# FindMeSAT_MB_1V2.net
KiCad netlist of a schematic drawn in EAGLE
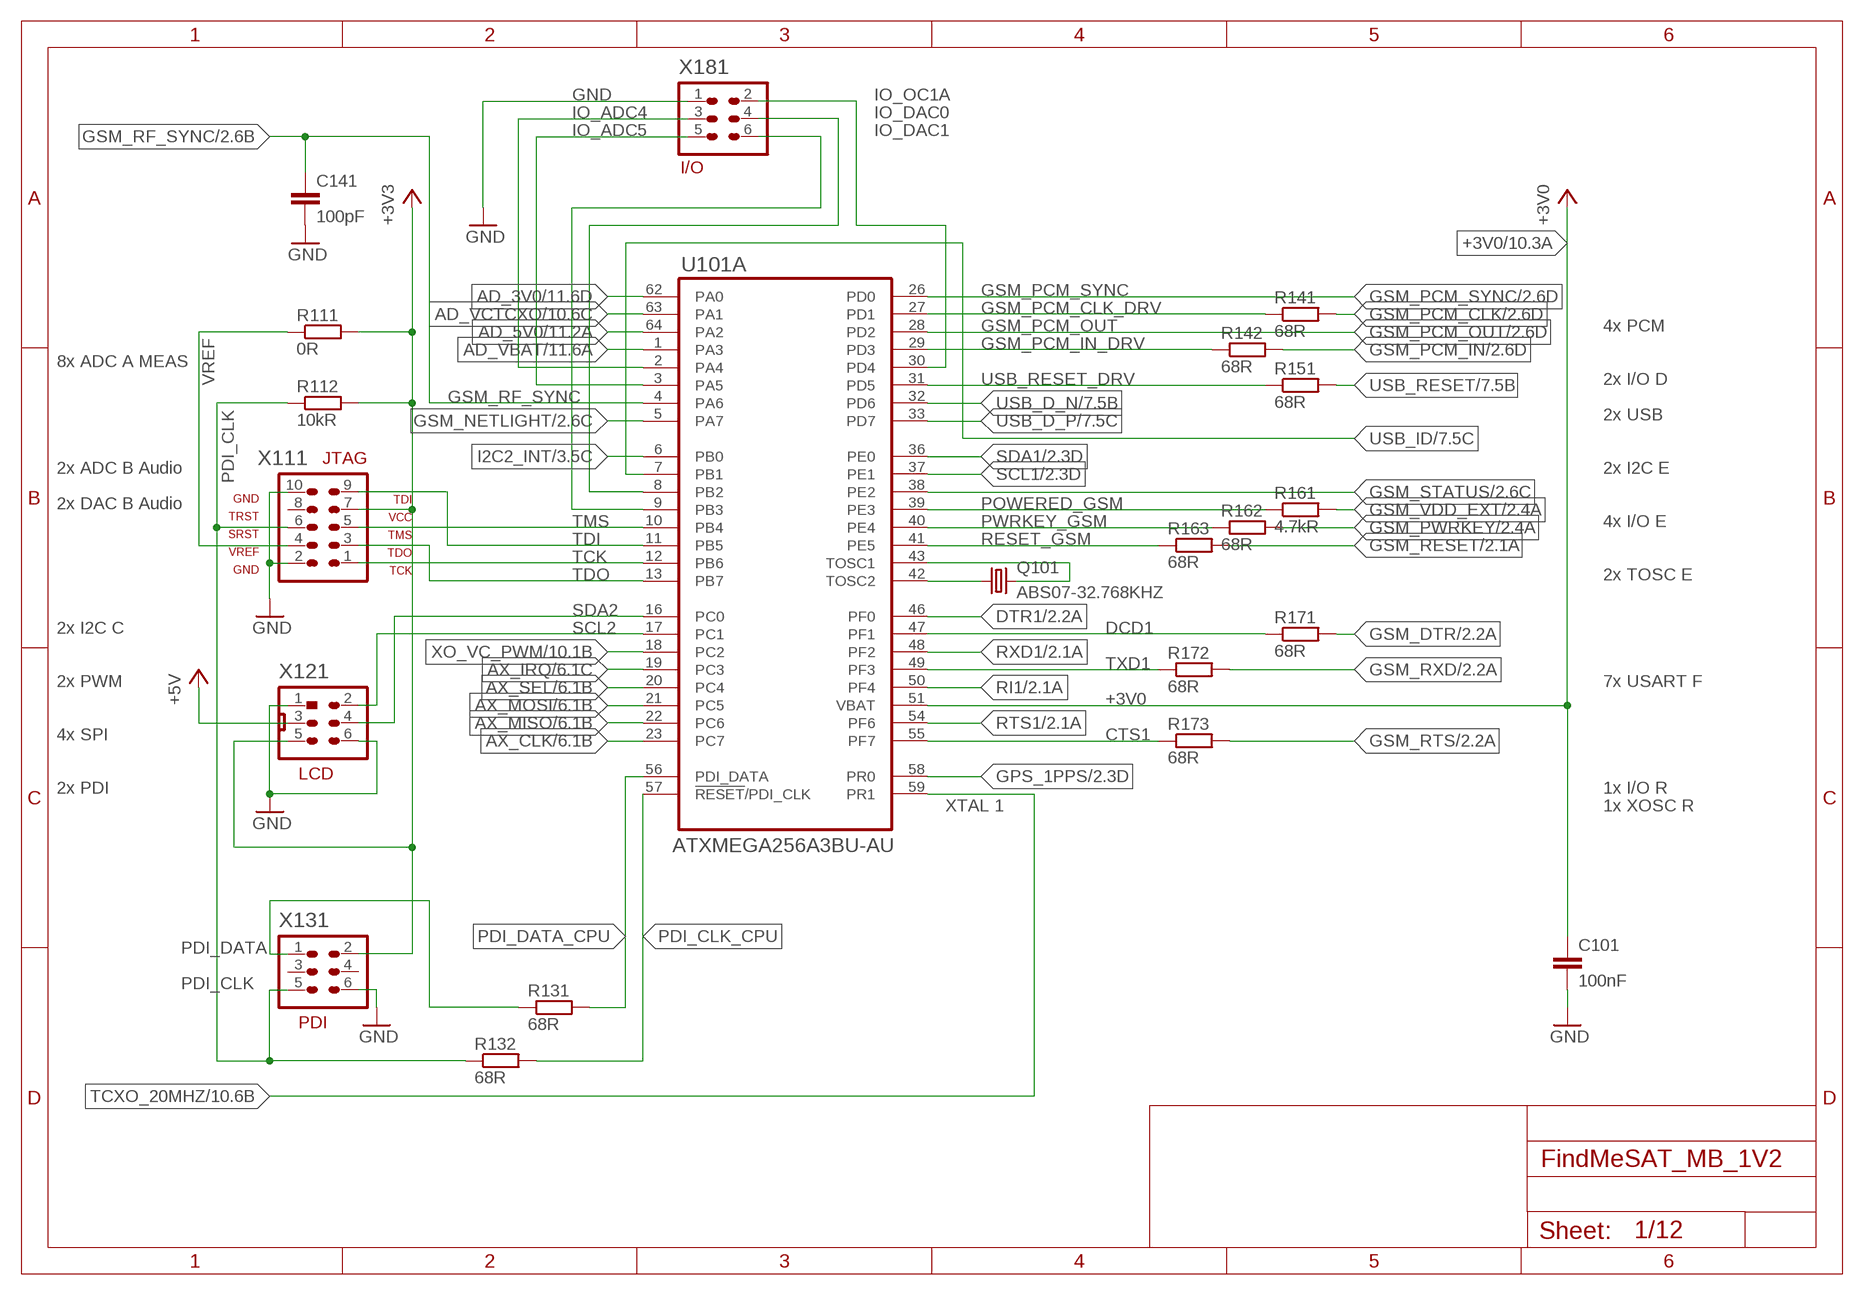
[diagram p0: schematic, sheet 1]
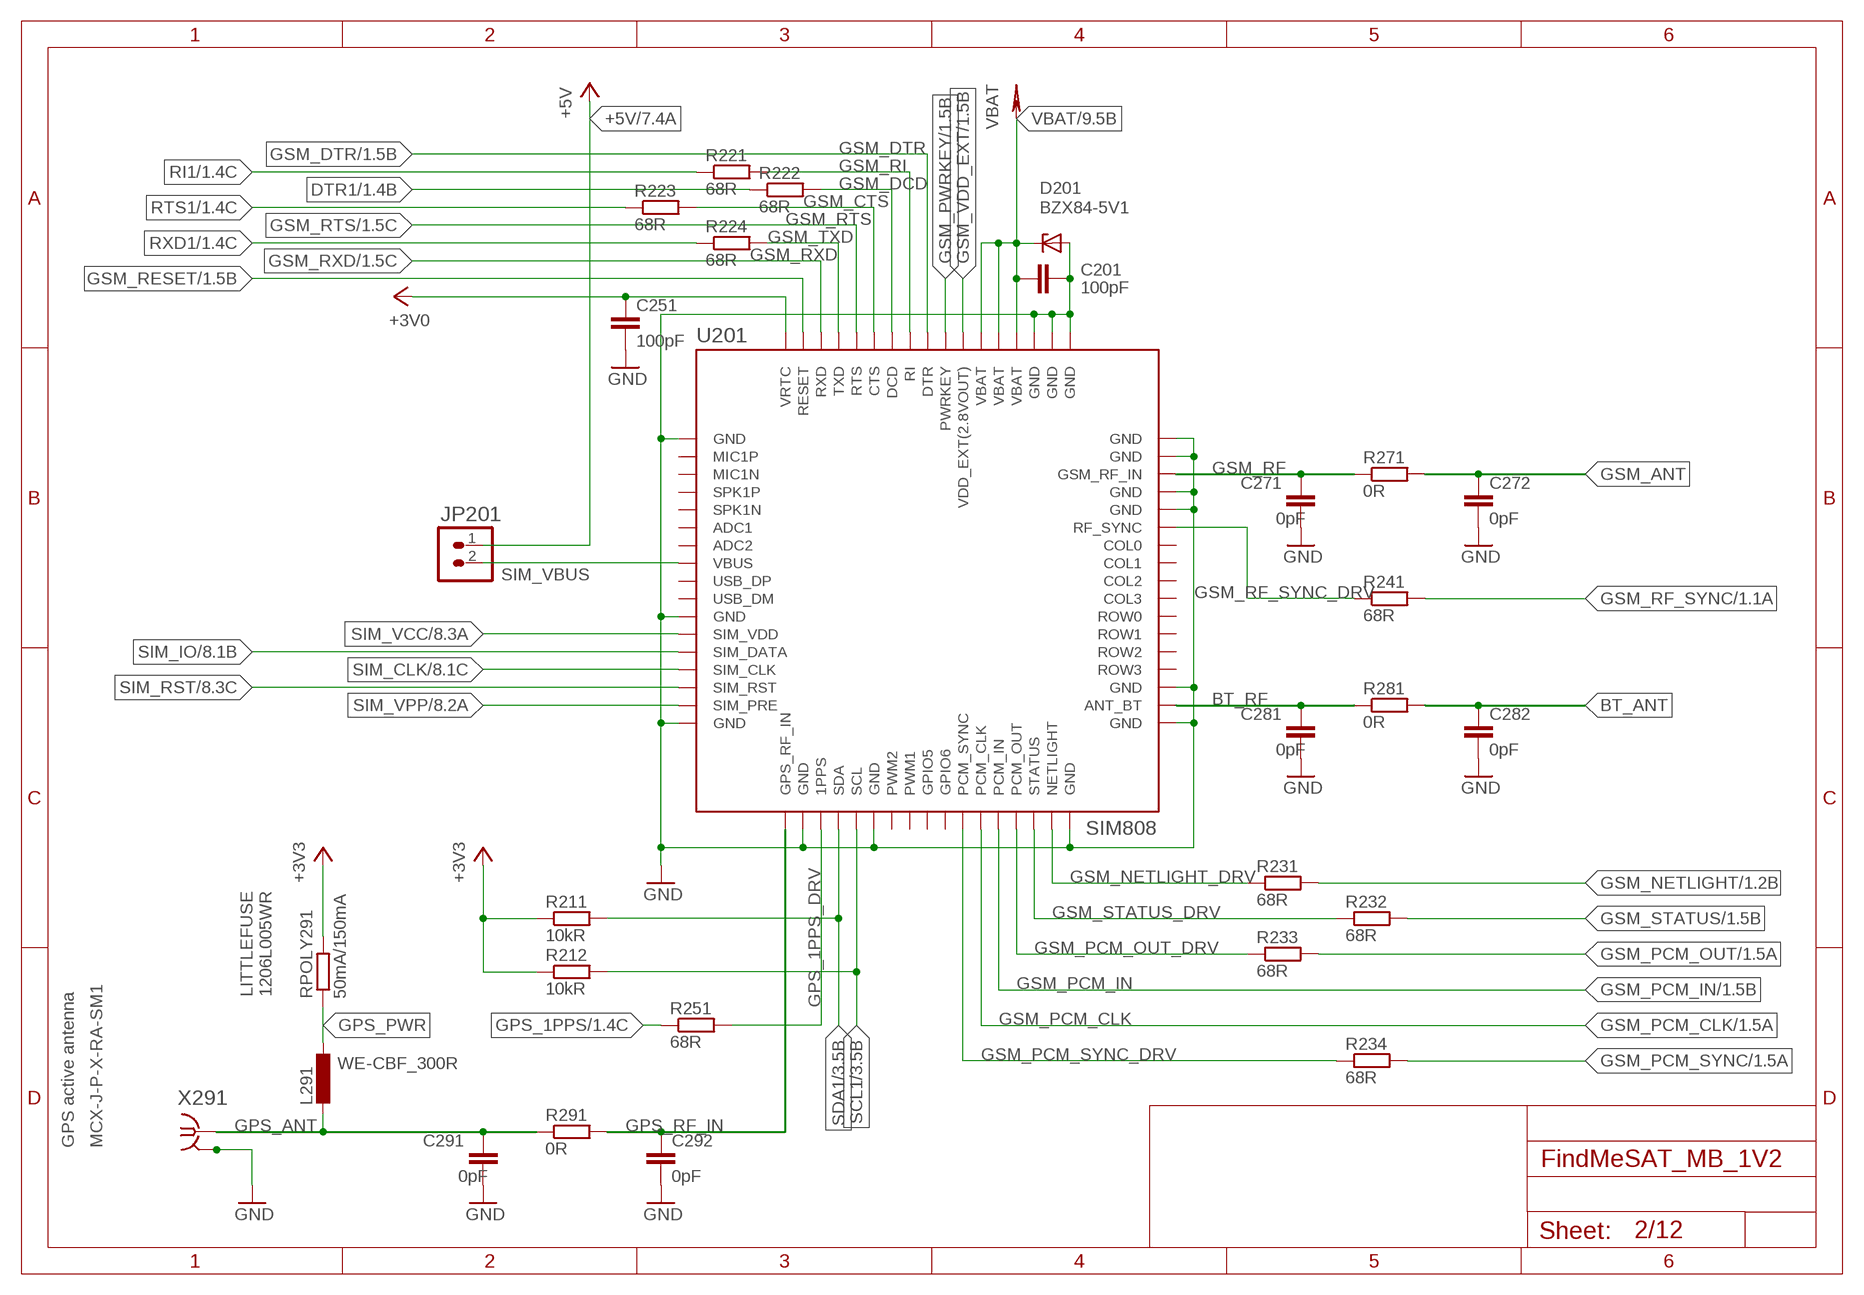
[diagram p1: schematic, sheet 2]
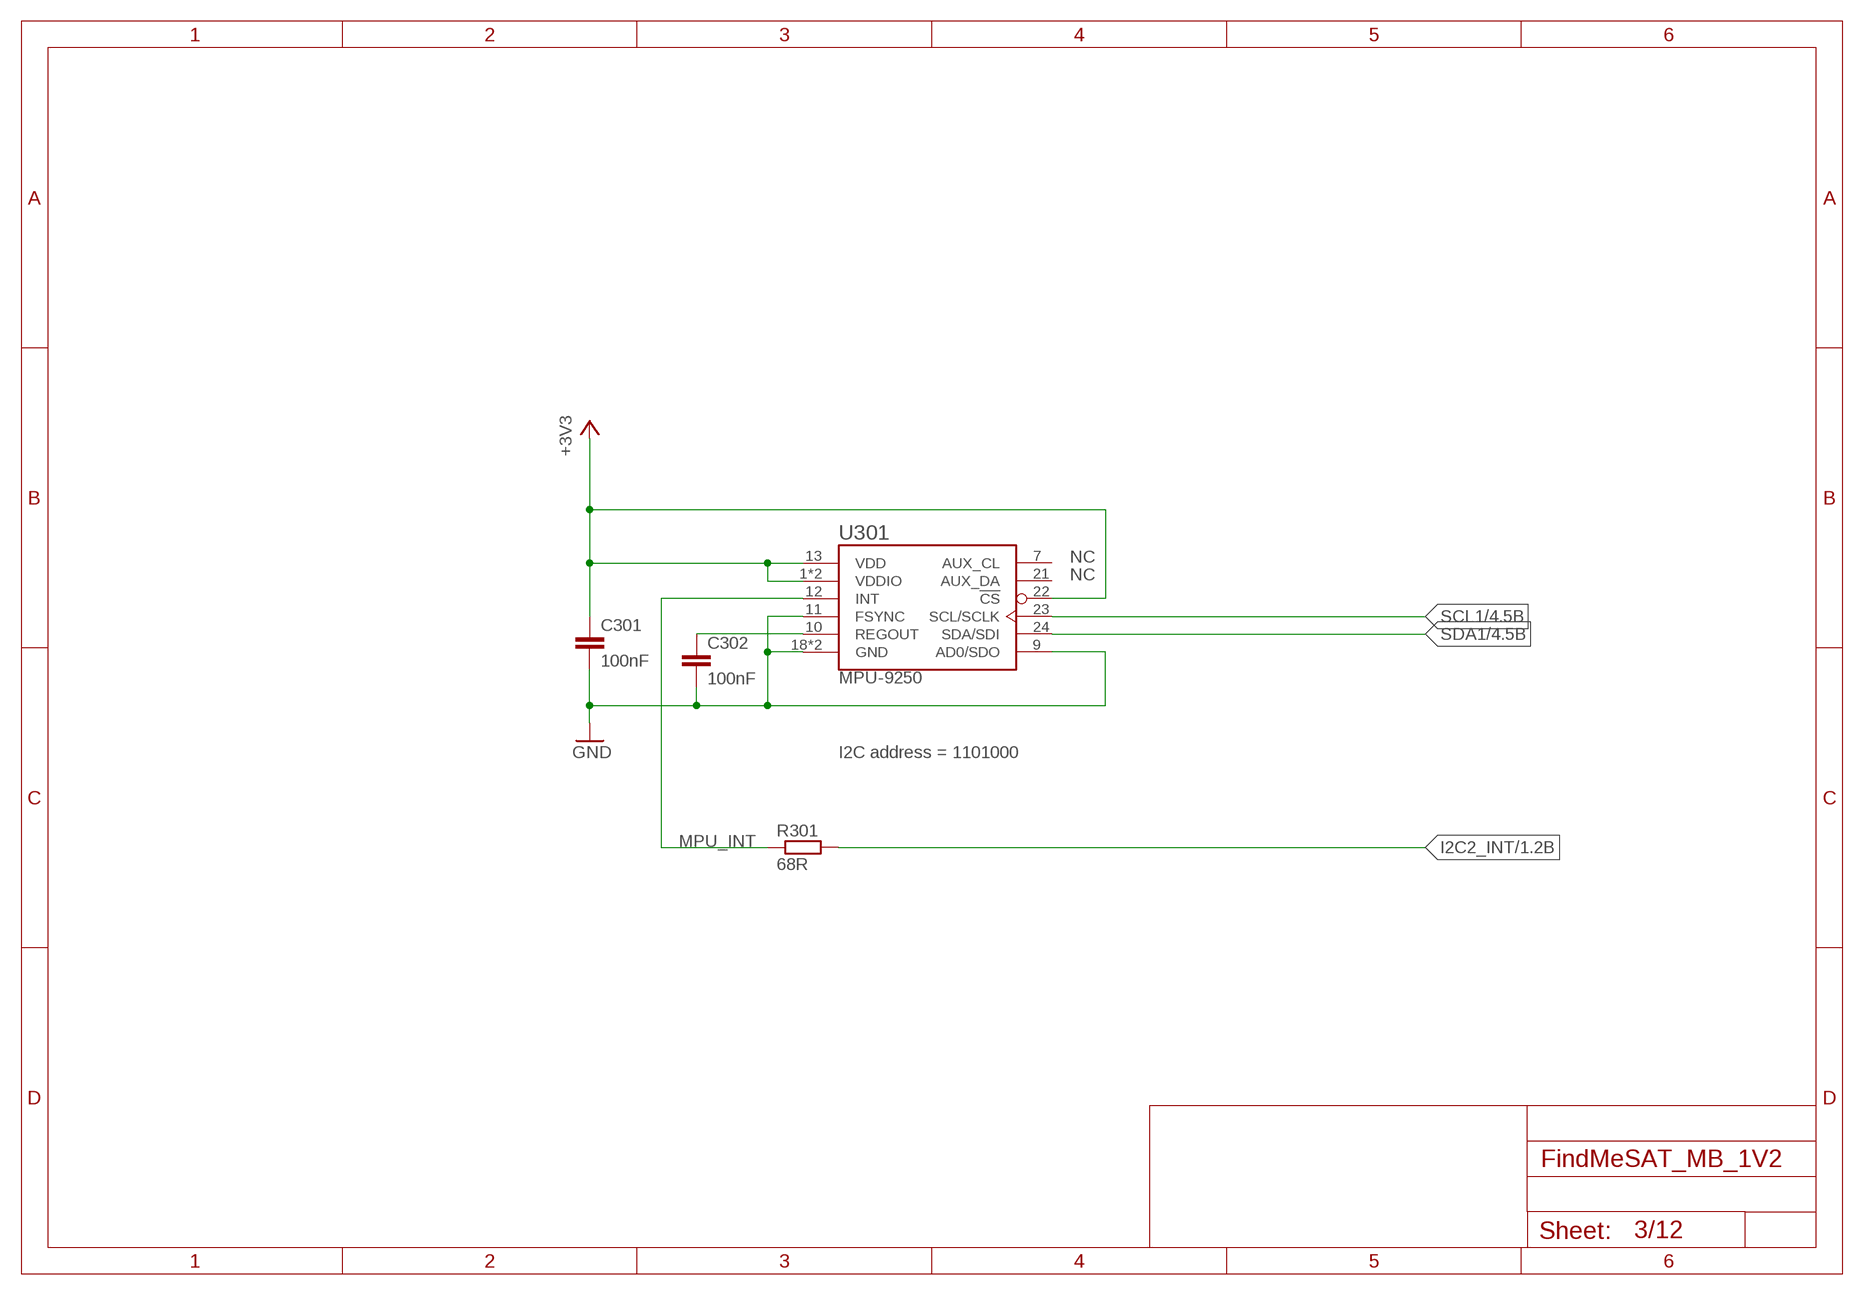
[diagram p2: schematic, sheet 3]
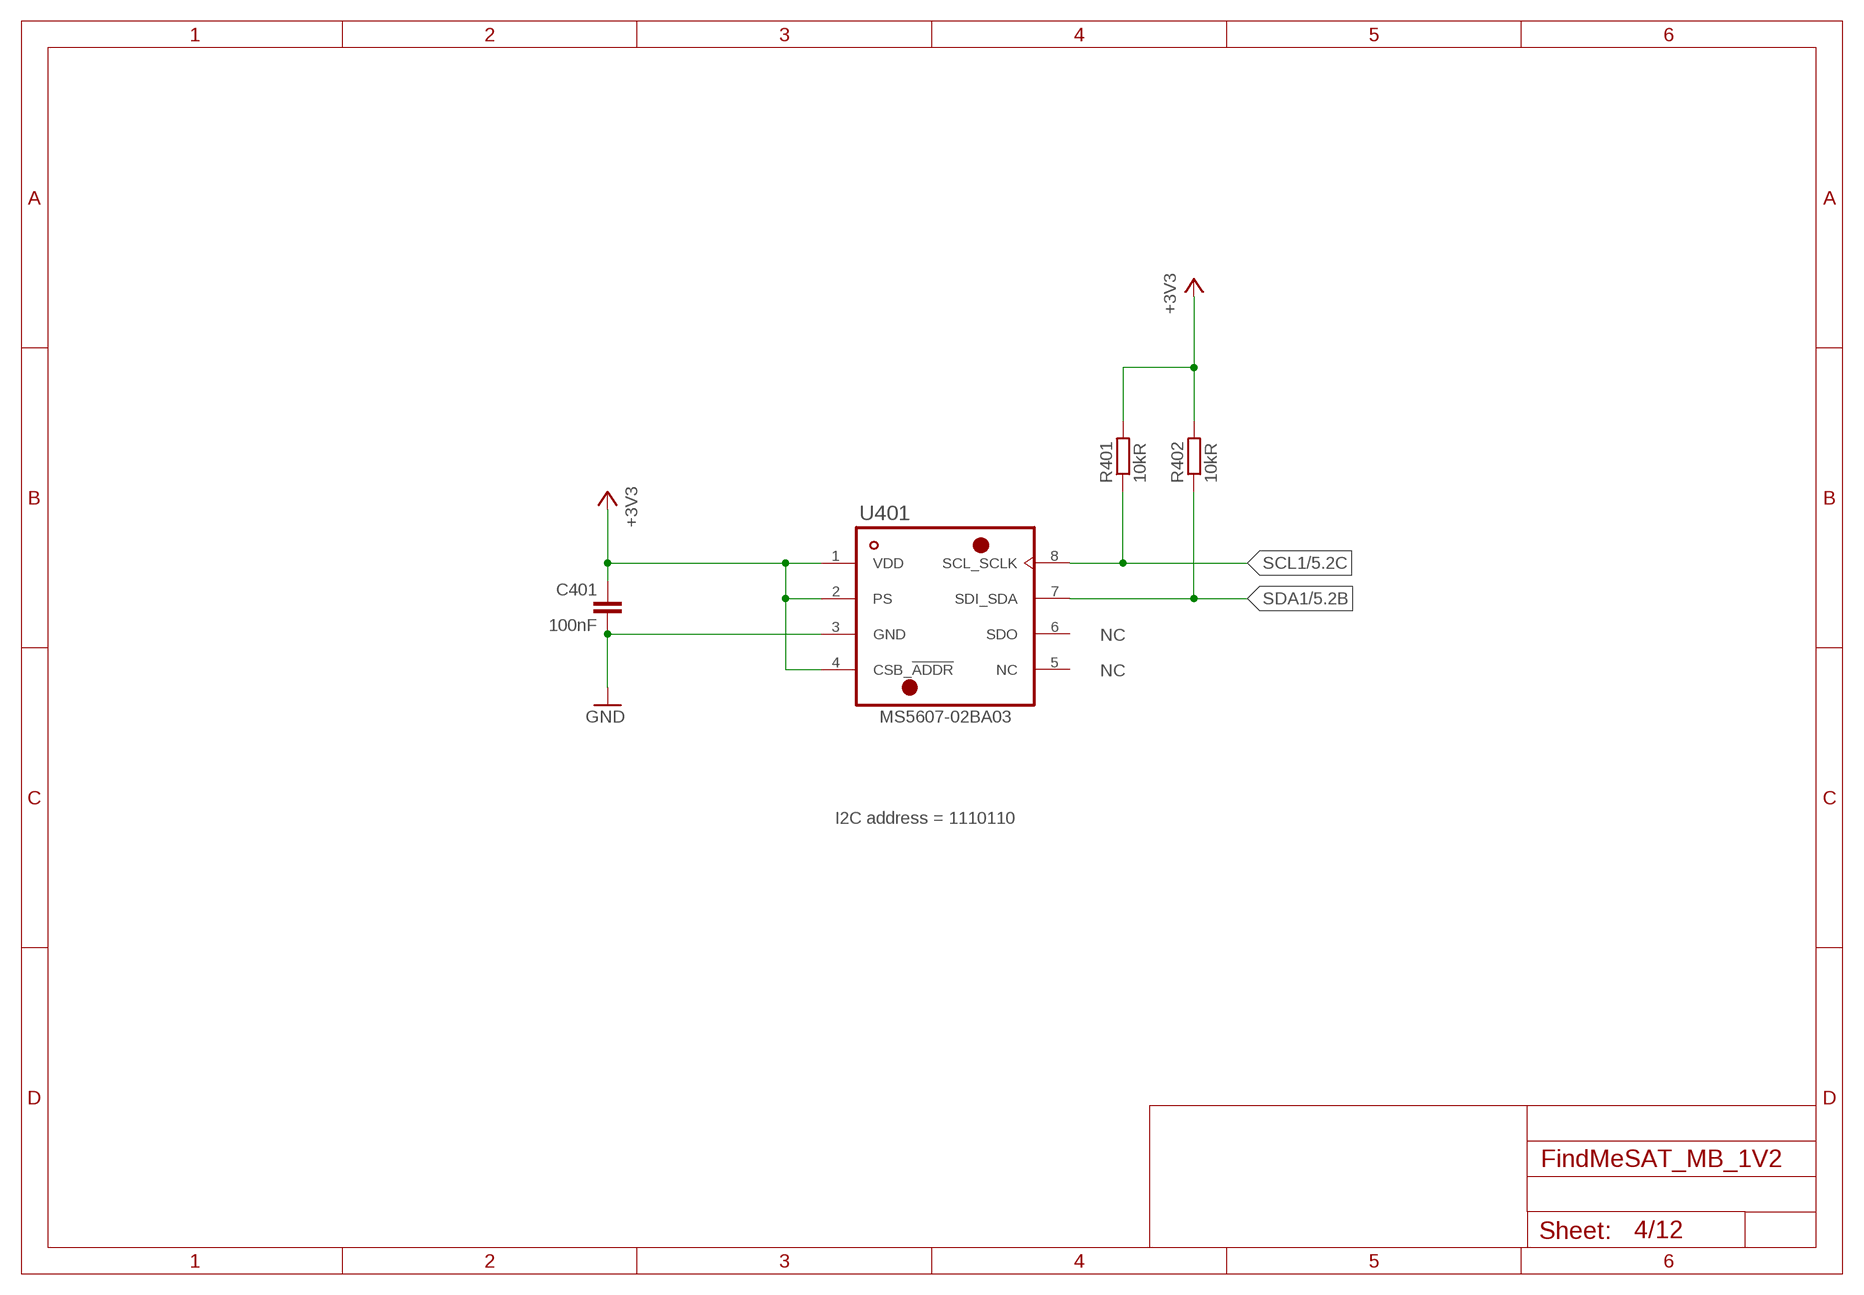
[diagram p3: schematic, sheet 4]
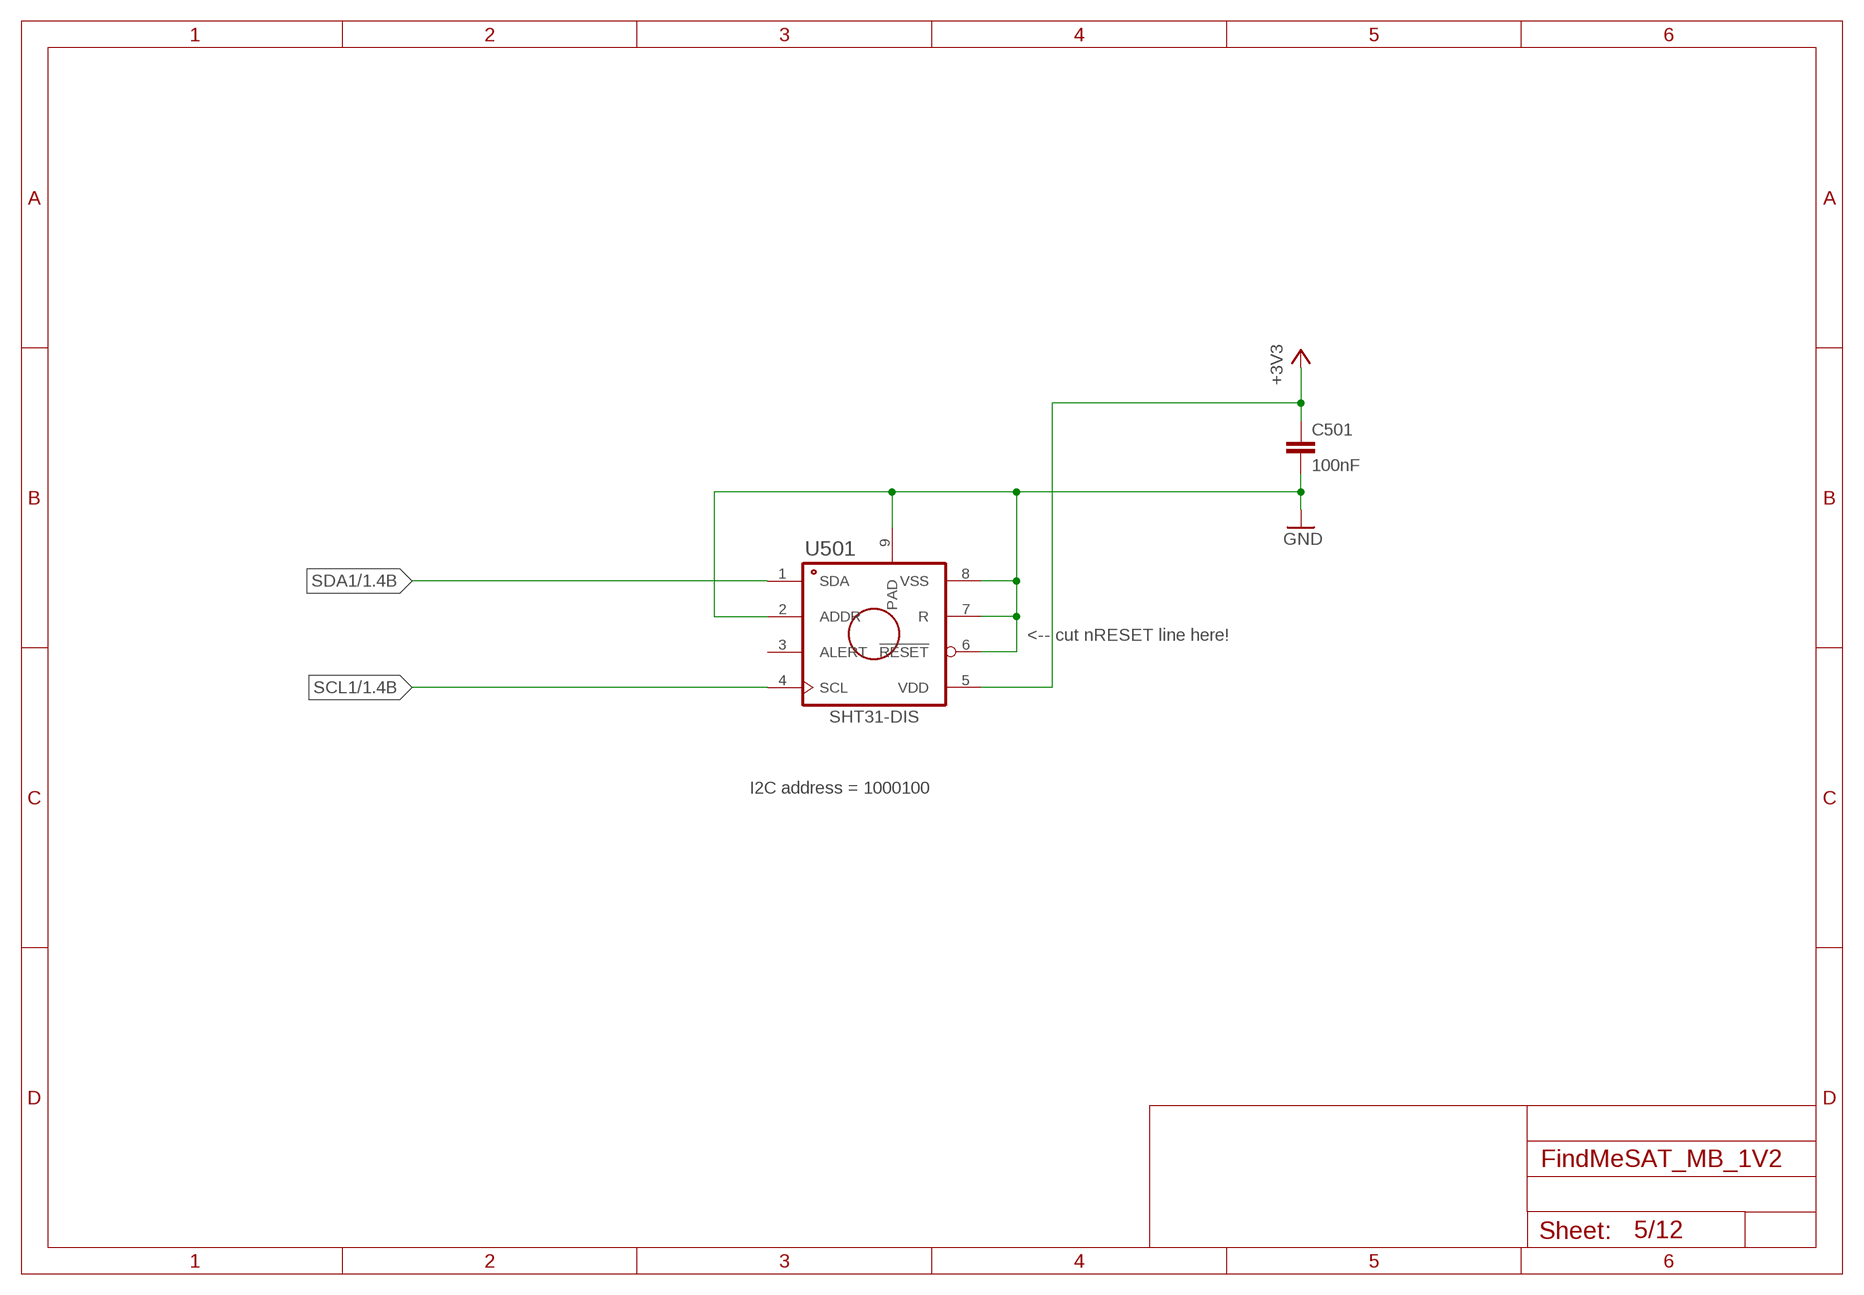
[diagram p4: schematic, sheet 5]
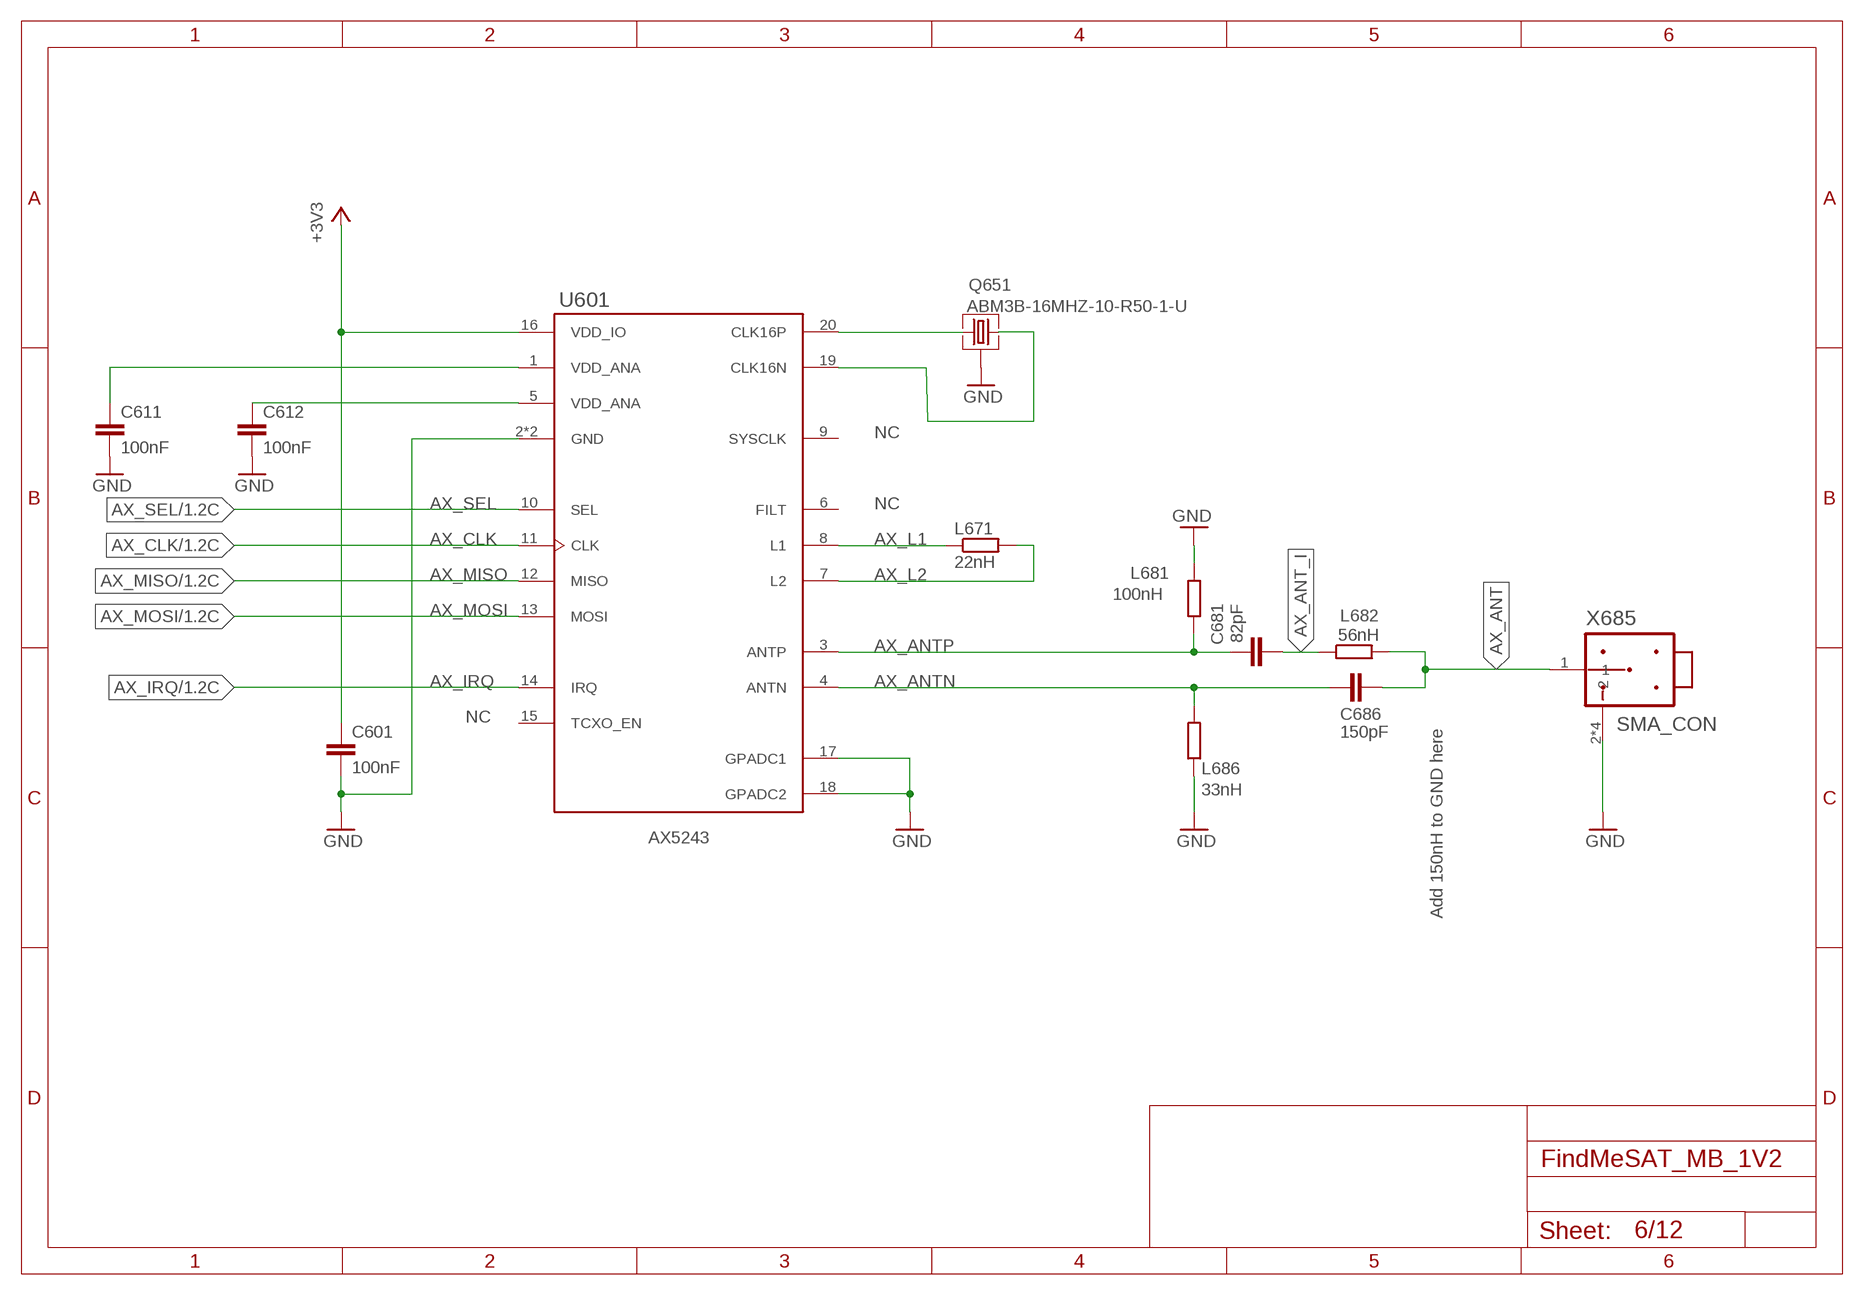
[diagram p5: schematic, sheet 6]
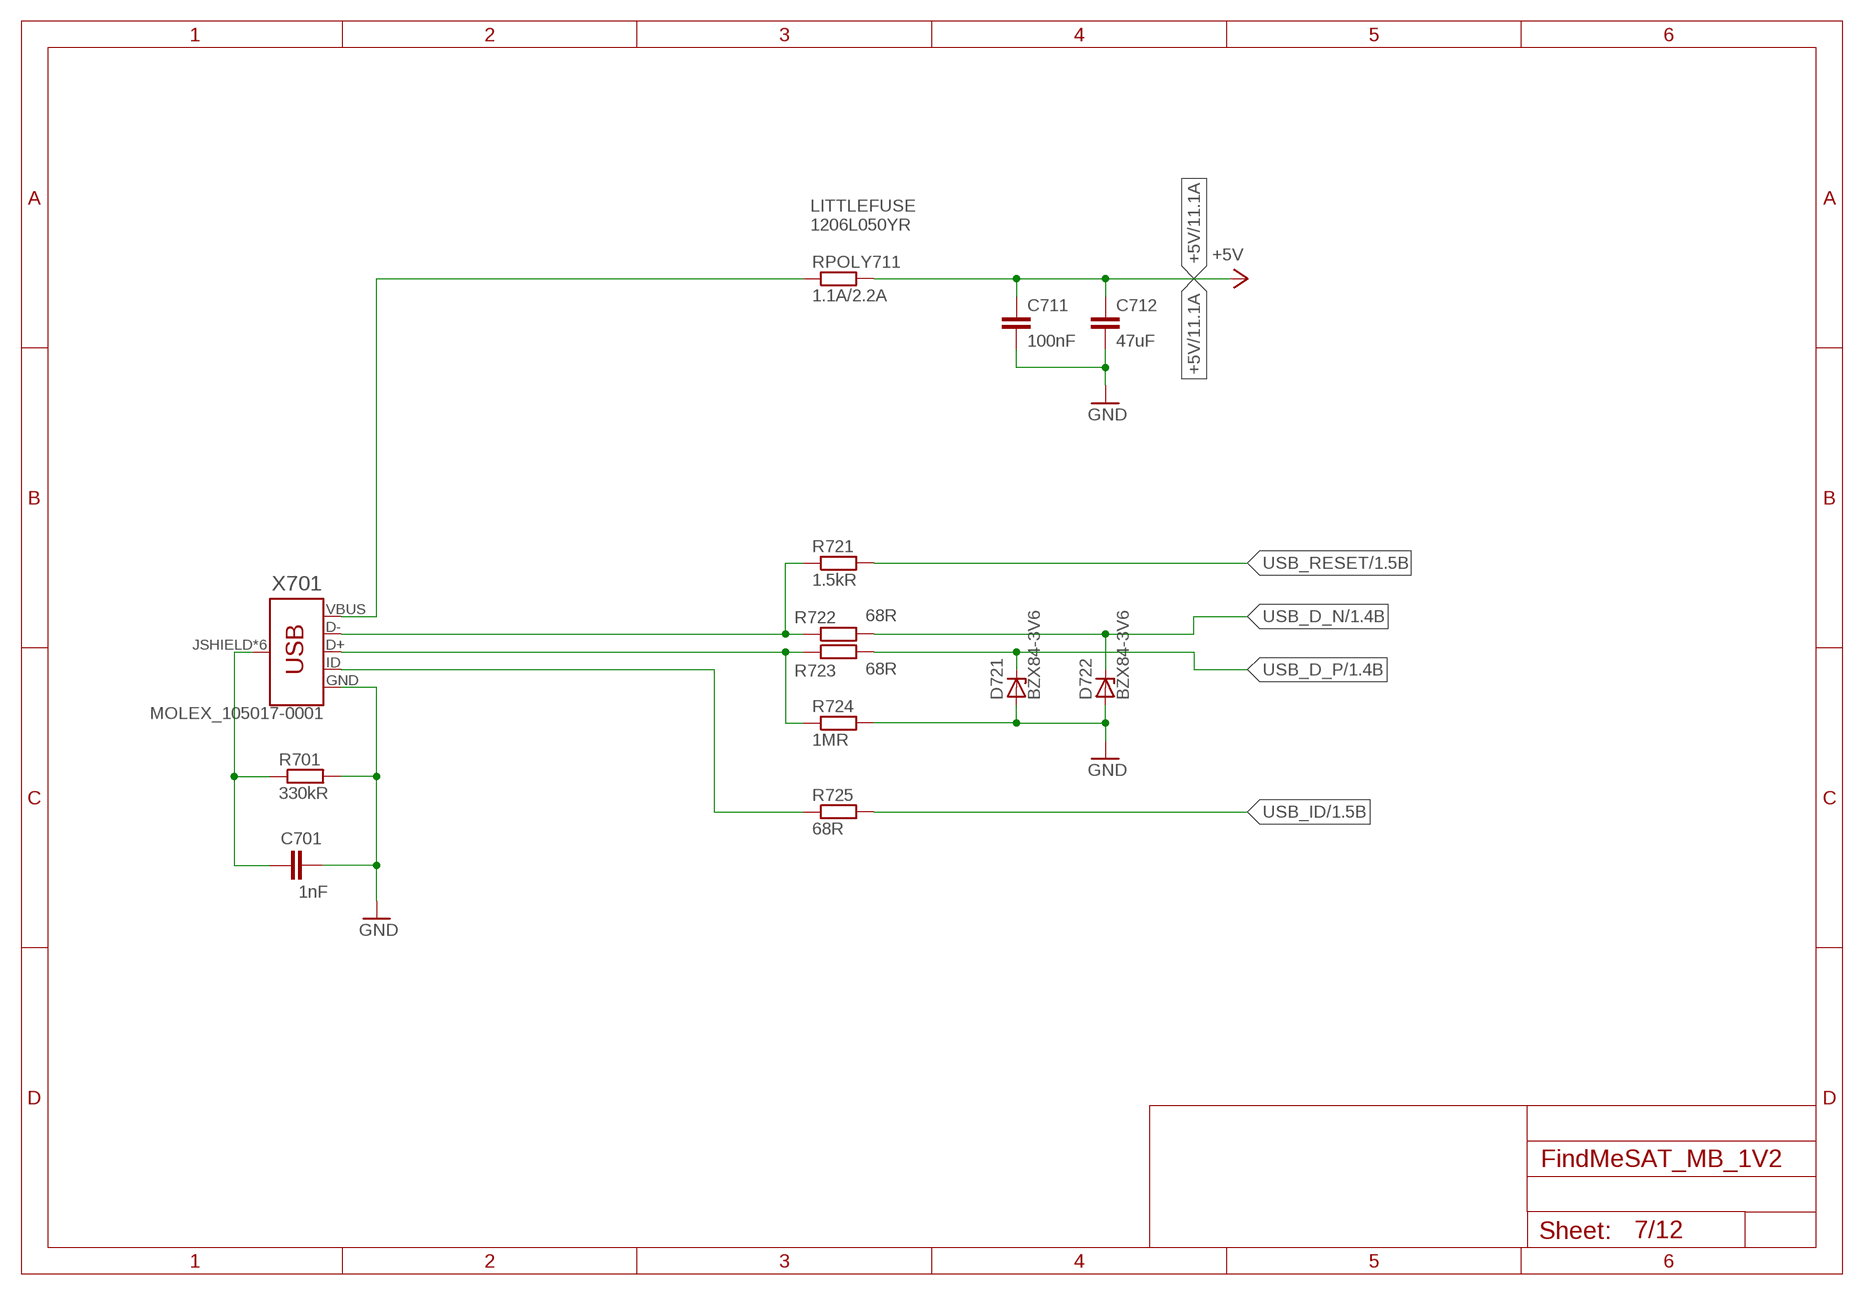
[diagram p6: schematic, sheet 7]
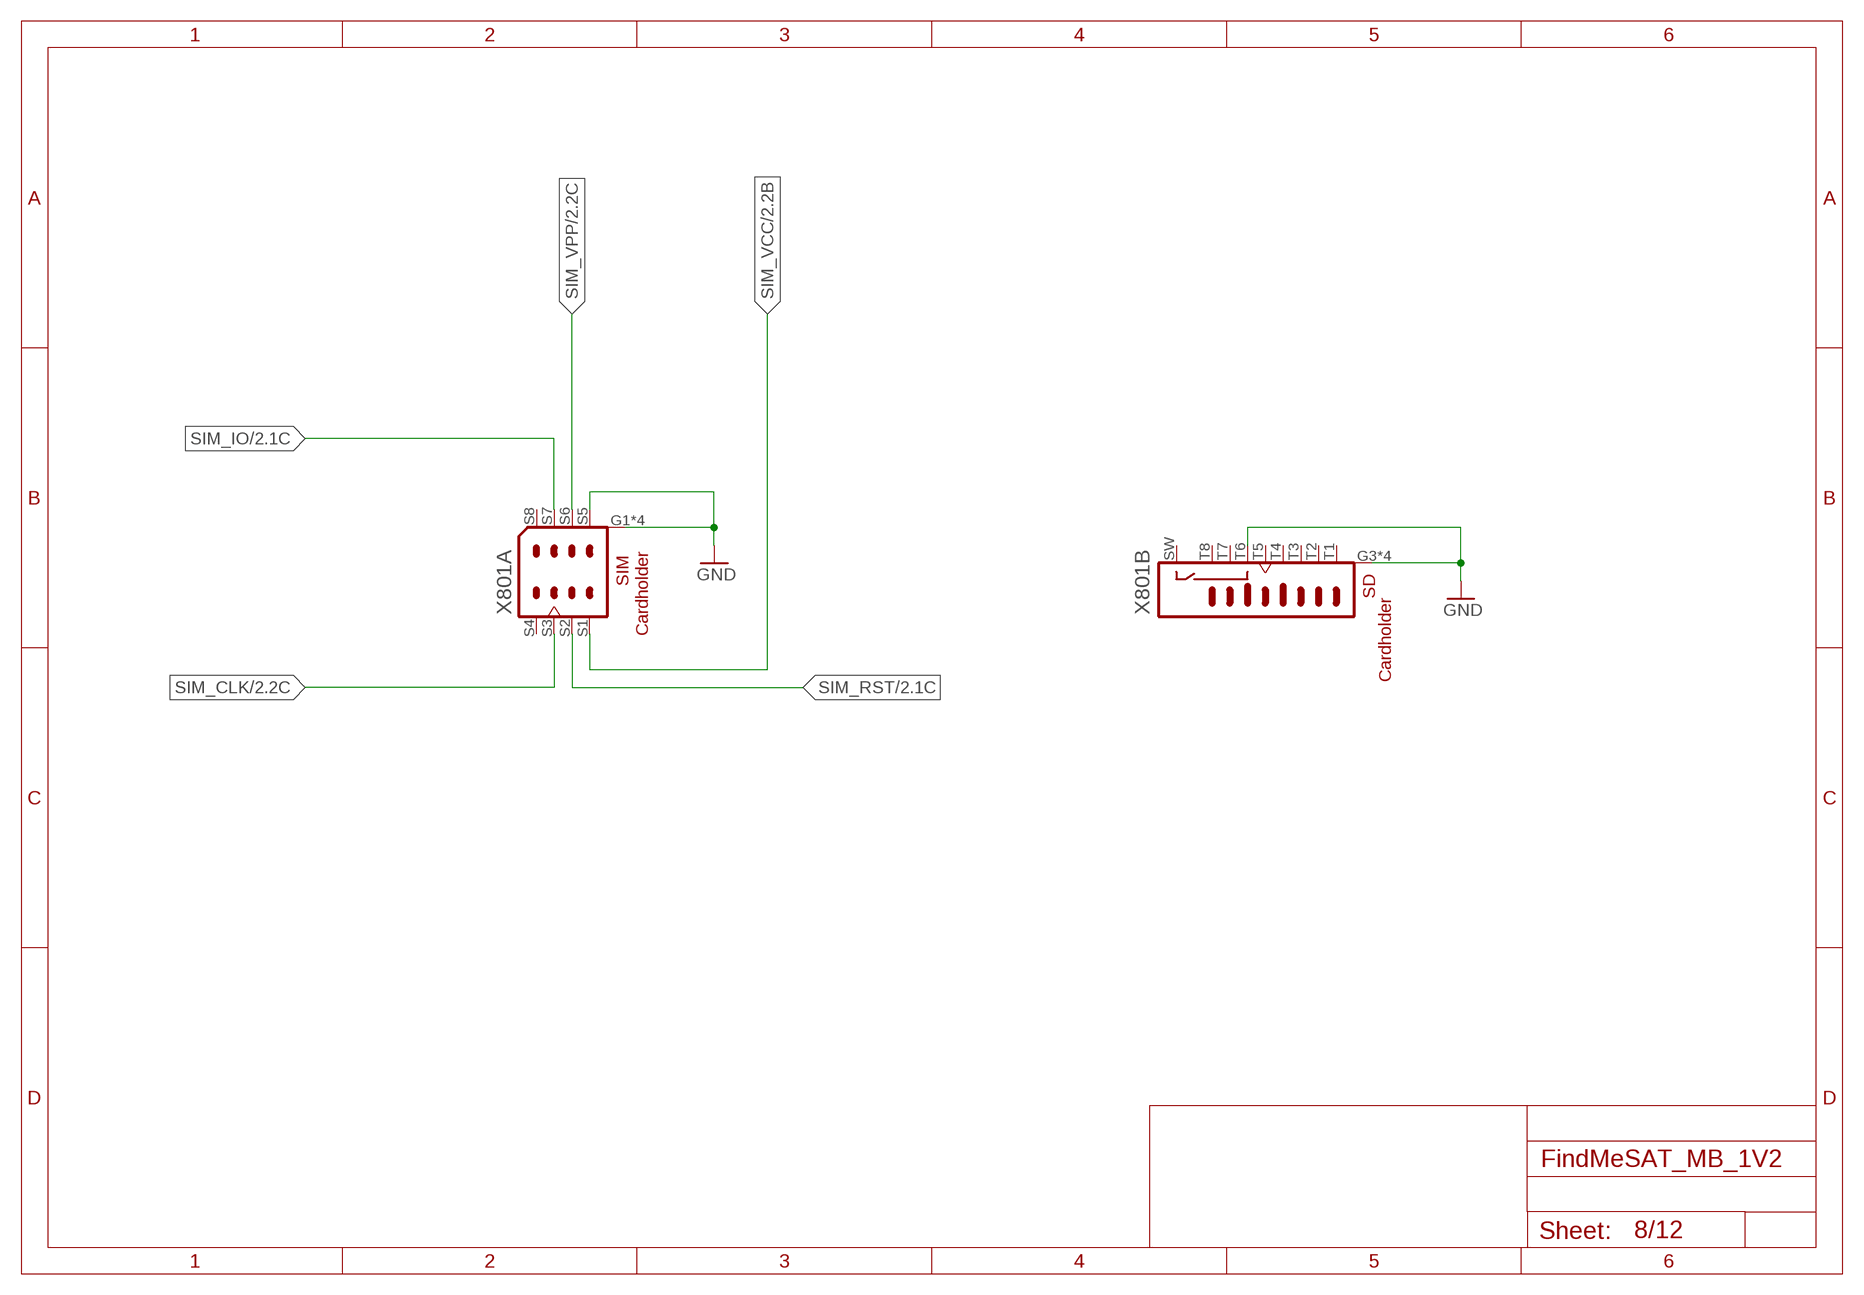
[diagram p7: schematic, sheet 8]
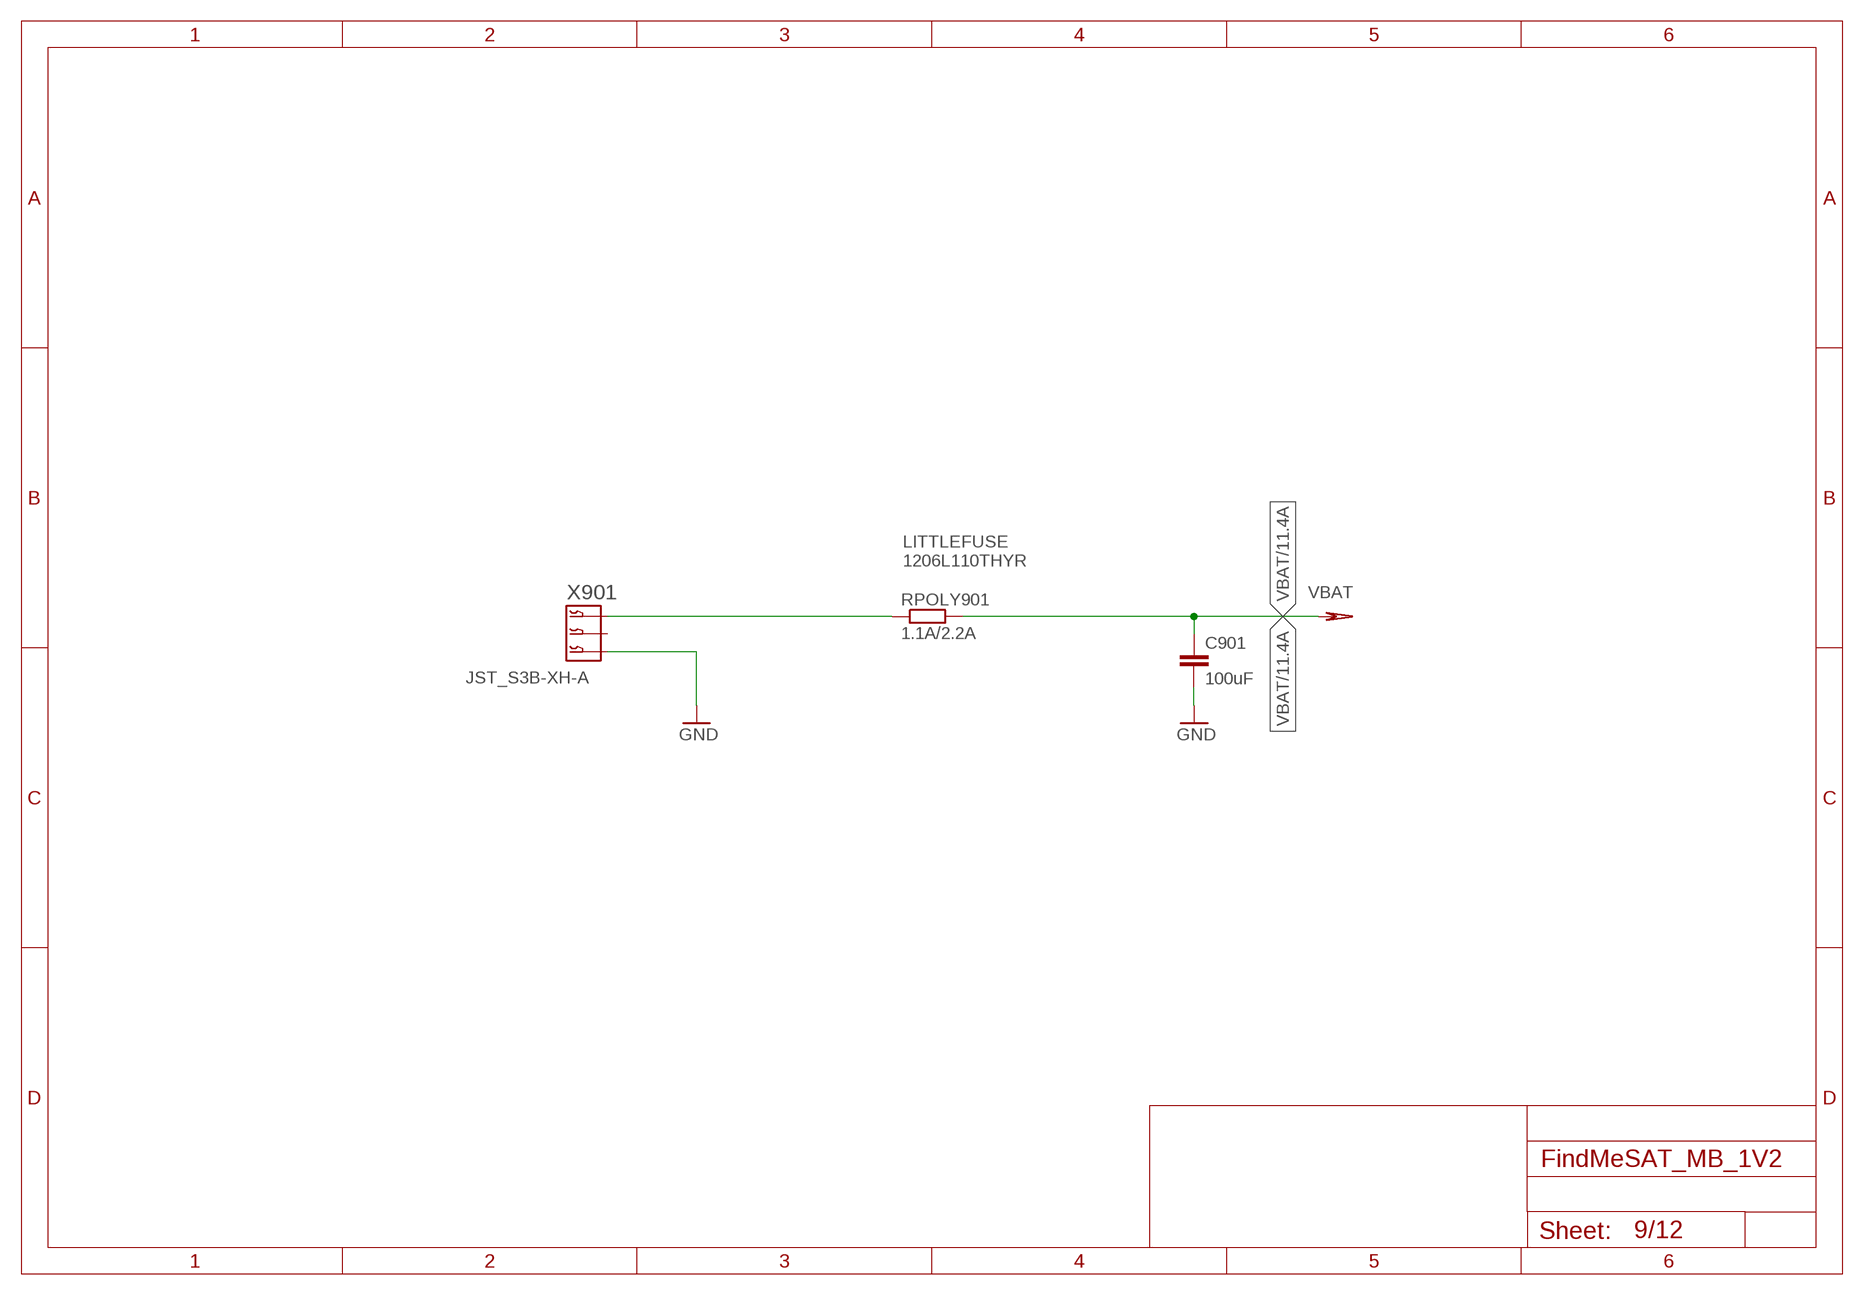
[diagram p8: schematic, sheet 9]
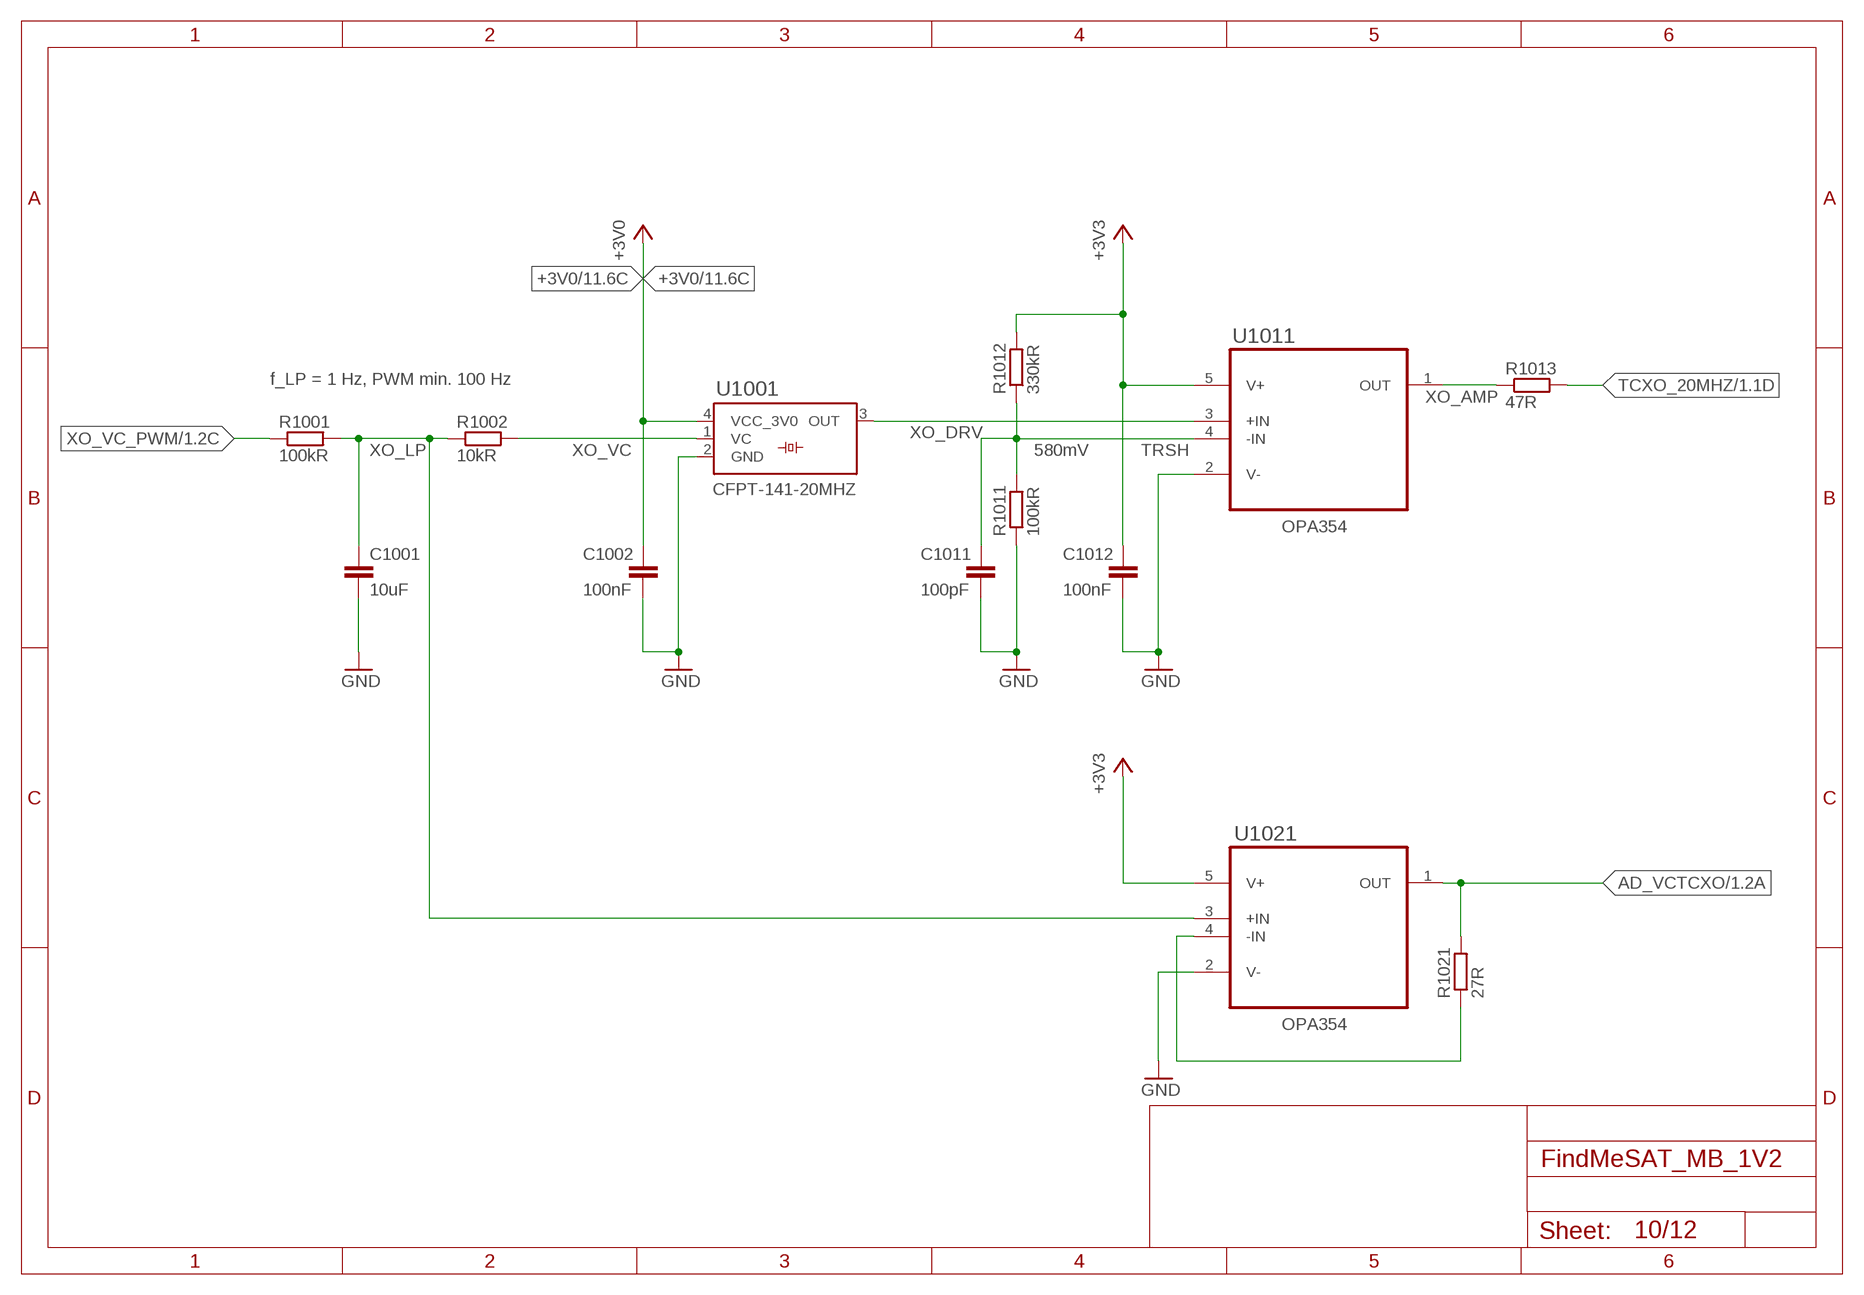
[diagram p9: schematic, sheet 10]
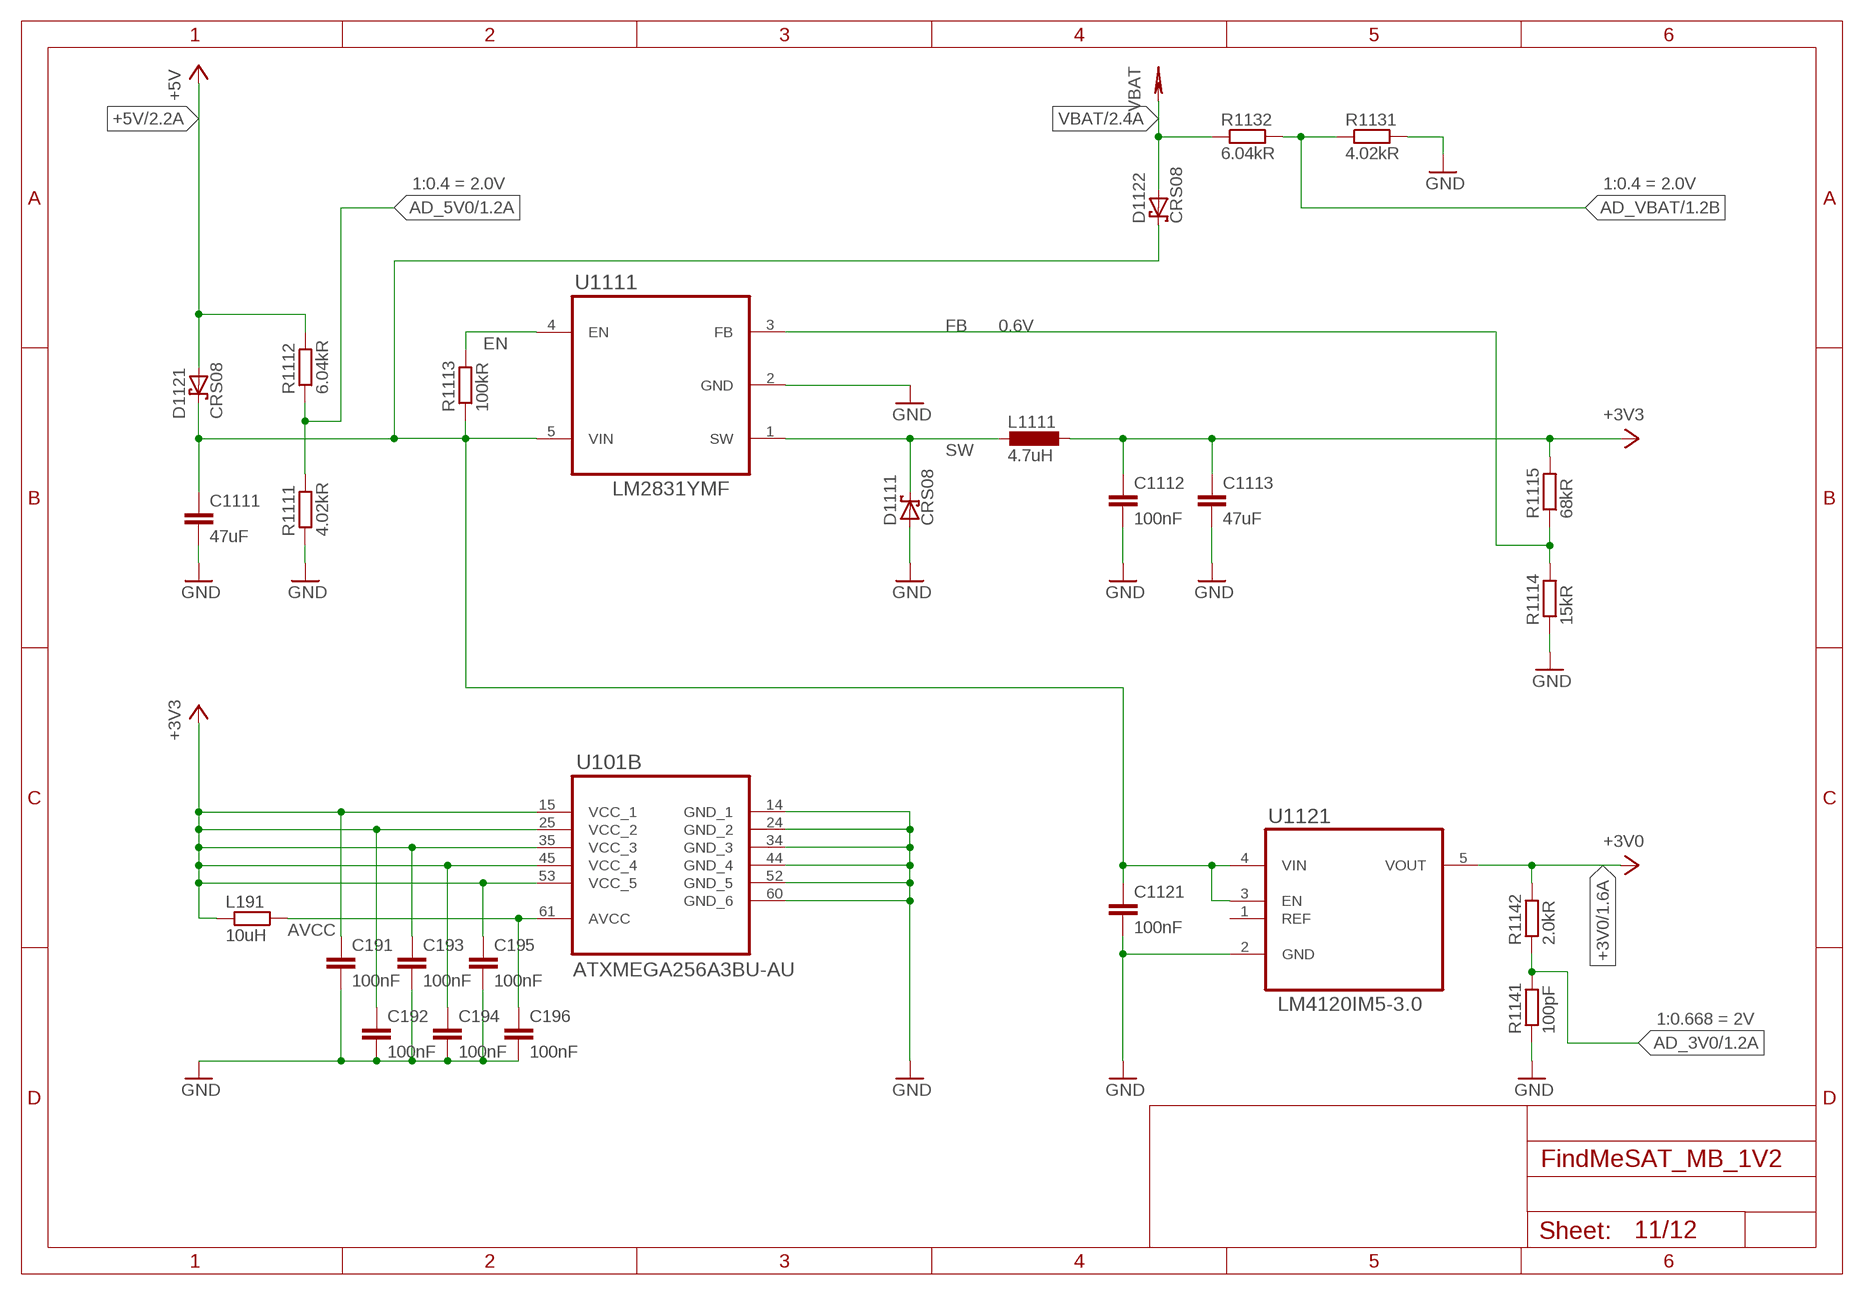
[diagram p10: schematic, sheet 11]
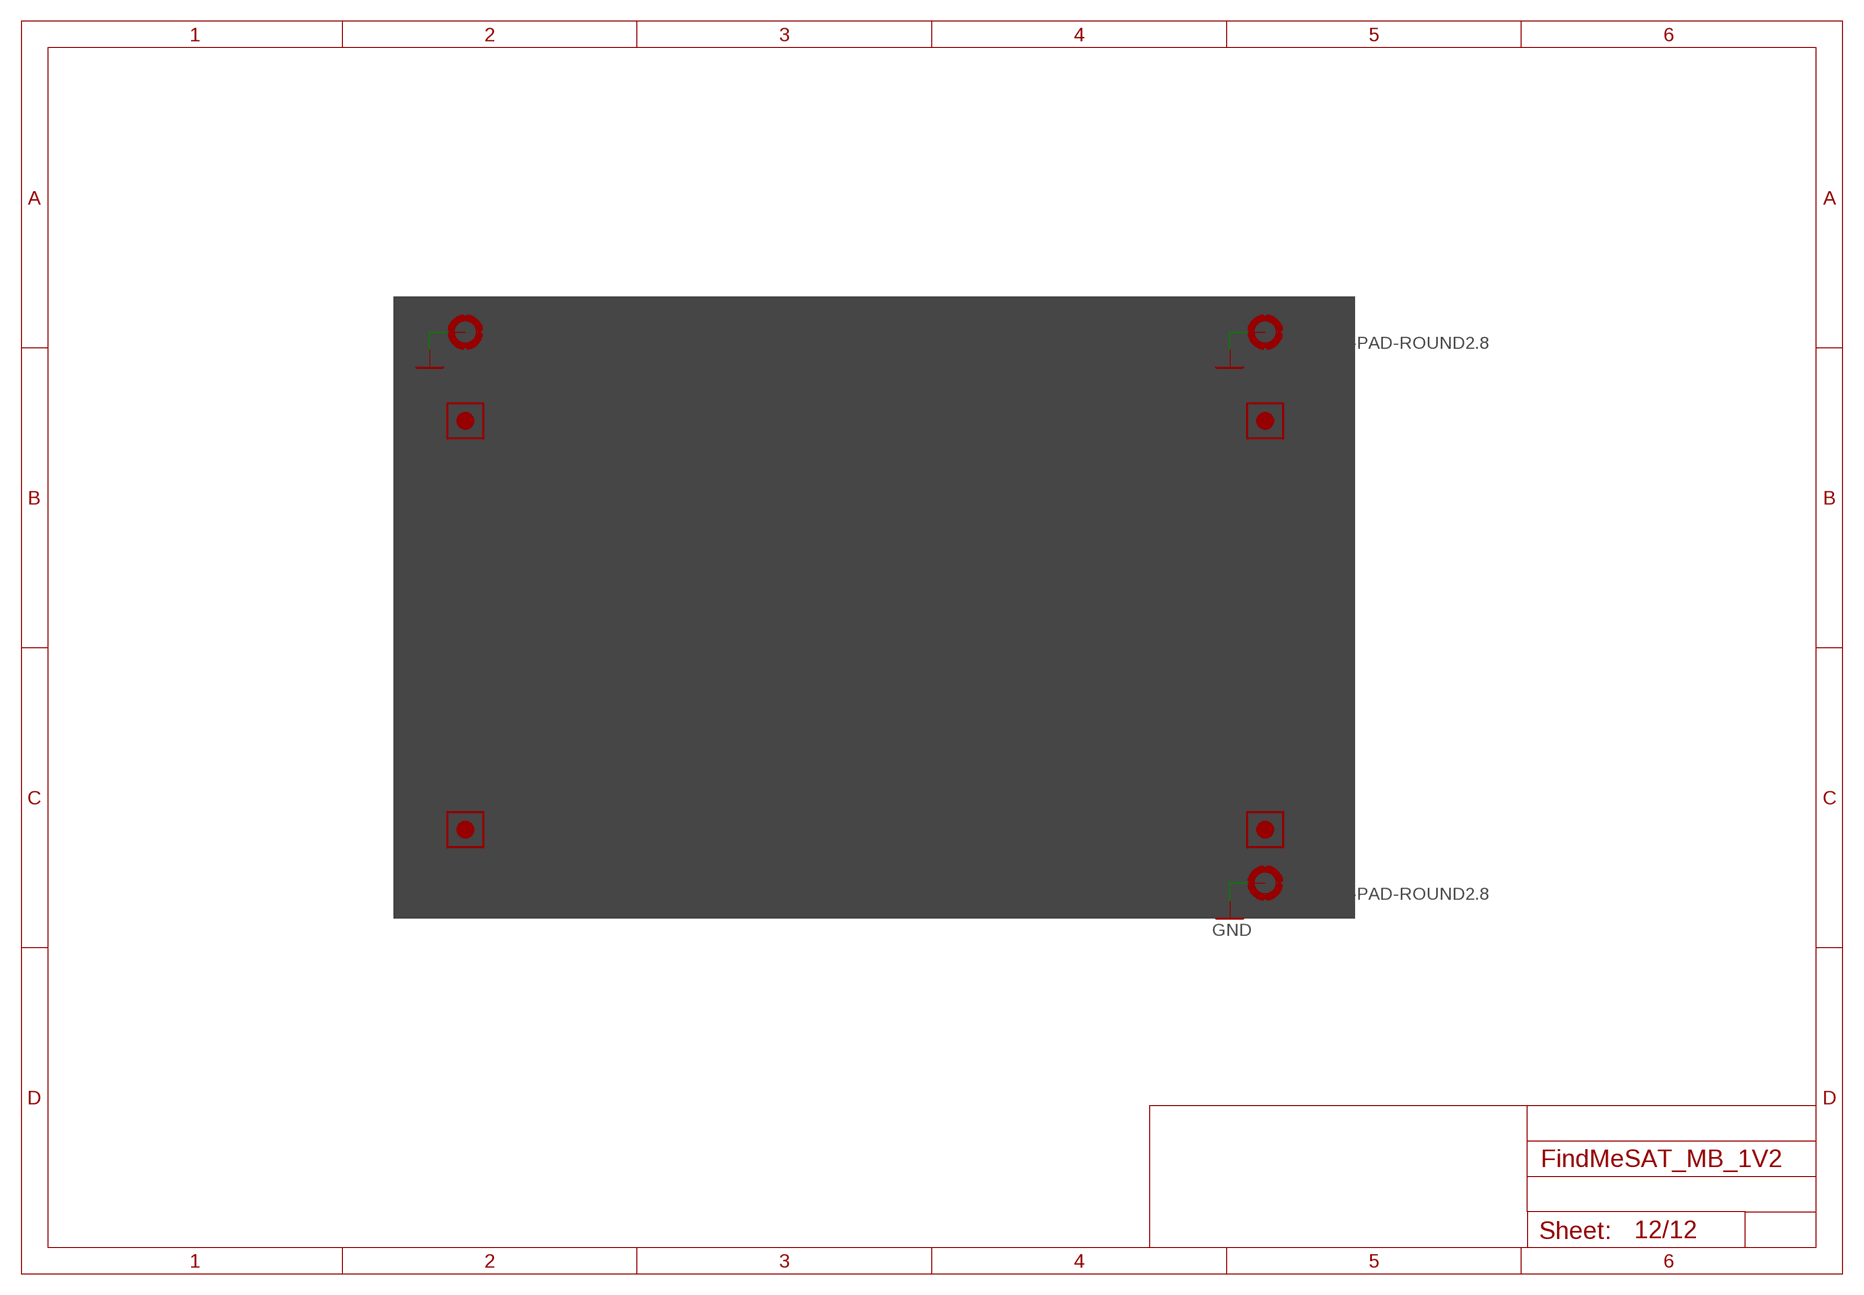
[diagram p11: schematic, sheet 12]

(export (version "E")
  (design (tool "Eeschema 10.0.6"))
  (components
    (comp (ref "C1001")
      (value "10uF")
      (footprint "eagle-import:C0603")
      (libsource (lib "eagle-import") (part "C-EUC0603"))
    )
    (comp (ref "C1002")
      (value "100nF")
      (footprint "eagle-import:C0603")
      (libsource (lib "eagle-import") (part "C-EUC0603"))
    )
    (comp (ref "C1011")
      (value "100pF")
      (footprint "eagle-import:C0603")
      (libsource (lib "eagle-import") (part "C-EUC0603"))
    )
    (comp (ref "C1012")
      (value "100nF")
      (footprint "eagle-import:C0603")
      (libsource (lib "eagle-import") (part "C-EUC0603"))
    )
    (comp (ref "R1001")
      (value "100kR")
      (footprint "eagle-import:R0603")
      (libsource (lib "eagle-import") (part "R-EU_R0603"))
    )
    (comp (ref "R1002")
      (value "10kR")
      (footprint "eagle-import:R0603")
      (libsource (lib "eagle-import") (part "R-EU_R0603"))
    )
    (comp (ref "R1011")
      (value "100kR")
      (footprint "eagle-import:R0603")
      (libsource (lib "eagle-import") (part "R-EU_R0603"))
    )
    (comp (ref "R1012")
      (value "330kR")
      (footprint "eagle-import:R0603")
      (libsource (lib "eagle-import") (part "R-EU_R0603"))
    )
    (comp (ref "R1013")
      (value "47R")
      (footprint "eagle-import:R0603")
      (libsource (lib "eagle-import") (part "R-EU_R0603"))
    )
    (comp (ref "R1021")
      (value "27R")
      (footprint "eagle-import:R0603")
      (libsource (lib "eagle-import") (part "R-EU_R0603"))
    )
    (comp (ref "U1001")
      (value "CFPT-141-20MHZ")
      (footprint "eagle-import:CFPT-141")
      (fields (field (name "MF") "IQD-FREQUENCY-PRODUCTS") (field (name "MPN") "LFTVXO022175"))
      (libsource (lib "eagle-import") (part "CFPT-141-20MHZ"))
    )
    (comp (ref "U1011")
      (value "OPA354")
      (footprint "eagle-import:SOT-23-5")
      (fields (field (name "MPN") "OPA354AIDBVT"))
      (libsource (lib "eagle-import") (part "OPA354"))
    )
    (comp (ref "U1021")
      (value "OPA354")
      (footprint "eagle-import:SOT-23-5")
      (fields (field (name "MPN") "OPA354AIDBVT"))
      (libsource (lib "eagle-import") (part "OPA354"))
    )
    (comp (ref "C101")
      (value "100nF")
      (footprint "eagle-import:C0603")
      (libsource (lib "eagle-import") (part "C-EUC0603"))
    )
    (comp (ref "C141")
      (value "100pF")
      (footprint "eagle-import:C0603")
      (libsource (lib "eagle-import") (part "C-EUC0603"))
    )
    (comp (ref "Q101")
      (value "ABS07-32.768KHZ")
      (footprint "eagle-import:ABS07")
      (fields (field (name "MANUFACTURER") "ABS07-32.768KHZ-1-T"))
      (libsource (lib "eagle-import") (part "ABS07-32.768KHZ"))
    )
    (comp (ref "R111")
      (value "0R")
      (footprint "eagle-import:R0805")
      (libsource (lib "eagle-import") (part "R-EU_R0805"))
    )
    (comp (ref "R112")
      (value "10kR")
      (footprint "eagle-import:R0603")
      (libsource (lib "eagle-import") (part "R-EU_R0603"))
    )
    (comp (ref "R131")
      (value "68R")
      (footprint "eagle-import:R0603")
      (libsource (lib "eagle-import") (part "R-EU_R0603"))
    )
    (comp (ref "R132")
      (value "68R")
      (footprint "eagle-import:R0603")
      (libsource (lib "eagle-import") (part "R-EU_R0603"))
    )
    (comp (ref "R141")
      (value "68R")
      (footprint "eagle-import:R0603")
      (libsource (lib "eagle-import") (part "R-EU_R0603"))
    )
    (comp (ref "R142")
      (value "68R")
      (footprint "eagle-import:R0603")
      (libsource (lib "eagle-import") (part "R-EU_R0603"))
    )
    (comp (ref "R151")
      (value "68R")
      (footprint "eagle-import:R0603")
      (libsource (lib "eagle-import") (part "R-EU_R0603"))
    )
    (comp (ref "R161")
      (value "4.7kR")
      (footprint "eagle-import:R0603")
      (libsource (lib "eagle-import") (part "R-EU_R0603"))
    )
    (comp (ref "R162")
      (value "68R")
      (footprint "eagle-import:R0603")
      (libsource (lib "eagle-import") (part "R-EU_R0603"))
    )
    (comp (ref "R163")
      (value "68R")
      (footprint "eagle-import:R0603")
      (libsource (lib "eagle-import") (part "R-EU_R0603"))
    )
    (comp (ref "R171")
      (value "68R")
      (footprint "eagle-import:R0603")
      (libsource (lib "eagle-import") (part "R-EU_R0603"))
    )
    (comp (ref "R172")
      (value "68R")
      (footprint "eagle-import:R0603")
      (libsource (lib "eagle-import") (part "R-EU_R0603"))
    )
    (comp (ref "R173")
      (value "68R")
      (footprint "eagle-import:R0603")
      (libsource (lib "eagle-import") (part "R-EU_R0603"))
    )
    (comp (ref "U101")
      (value "ATXMEGA256A3BU-AU")
      (footprint "eagle-import:QFP80P1600X1600X120-64N")
      (libsource (lib "eagle-import") (part "ATXMEGA256A3BU-AU"))
    )
    (comp (ref "X111")
      (value "AVR-JTAG-10")
      (footprint "eagle-import:2X05")
      (libsource (lib "eagle-import") (part "AVR-JTAG-10"))
    )
    (comp (ref "X121")
      (value "MOLEX_90130_2X03")
      (footprint "eagle-import:MOLEX_90130_2X03")
      (libsource (lib "eagle-import") (part "MOLEX_90130_2X03"))
    )
    (comp (ref "X131")
      (value "HEADER-2X3")
      (footprint "eagle-import:2X03")
      (libsource (lib "eagle-import") (part "HEADER-2X3"))
    )
    (comp (ref "X181")
      (value "HEADER-2X3")
      (footprint "eagle-import:2X03")
      (libsource (lib "eagle-import") (part "HEADER-2X3"))
    )
    (comp (ref "C901")
      (value "100uF")
      (footprint "eagle-import:C0805")
      (libsource (lib "eagle-import") (part "C-EUC0805"))
    )
    (comp (ref "RPOLY901")
      (value "1.1A/2.2A")
      (footprint "eagle-import:M1206")
      (libsource (lib "eagle-import") (part "R-EU_M1206"))
    )
    (comp (ref "X901")
      (value "JST_S3B-XH-A")
      (footprint "eagle-import:JST_S3B-XH-A")
      (libsource (lib "eagle-import") (part "JST_S3B-XH-A"))
    )
    (comp (ref "C191")
      (value "100nF")
      (footprint "eagle-import:C0603")
      (libsource (lib "eagle-import") (part "C-EUC0603"))
    )
    (comp (ref "C192")
      (value "100nF")
      (footprint "eagle-import:C0603")
      (libsource (lib "eagle-import") (part "C-EUC0603"))
    )
    (comp (ref "C193")
      (value "100nF")
      (footprint "eagle-import:C0603")
      (libsource (lib "eagle-import") (part "C-EUC0603"))
    )
    (comp (ref "C194")
      (value "100nF")
      (footprint "eagle-import:C0603")
      (libsource (lib "eagle-import") (part "C-EUC0603"))
    )
    (comp (ref "C195")
      (value "100nF")
      (footprint "eagle-import:C0603")
      (libsource (lib "eagle-import") (part "C-EUC0603"))
    )
    (comp (ref "C196")
      (value "100nF")
      (footprint "eagle-import:C0603")
      (libsource (lib "eagle-import") (part "C-EUC0603"))
    )
    (comp (ref "C1111")
      (value "47uF")
      (footprint "eagle-import:C0805")
      (libsource (lib "eagle-import") (part "C-EUC0805"))
    )
    (comp (ref "C1112")
      (value "100nF")
      (footprint "eagle-import:C0603")
      (libsource (lib "eagle-import") (part "C-EUC0603"))
    )
    (comp (ref "C1113")
      (value "47uF")
      (footprint "eagle-import:C0805")
      (libsource (lib "eagle-import") (part "C-EUC0805"))
    )
    (comp (ref "C1121")
      (value "100nF")
      (footprint "eagle-import:C0603")
      (libsource (lib "eagle-import") (part "C-EUC0603"))
    )
    (comp (ref "D1111")
      (value "CRS08")
      (footprint "eagle-import:SOD80C")
      (libsource (lib "eagle-import") (part "CRS08"))
    )
    (comp (ref "D1121")
      (value "CRS08")
      (footprint "eagle-import:SOD80C")
      (libsource (lib "eagle-import") (part "CRS08"))
    )
    (comp (ref "D1122")
      (value "CRS08")
      (footprint "eagle-import:SOD80C")
      (libsource (lib "eagle-import") (part "CRS08"))
    )
    (comp (ref "L191")
      (value "10uH")
      (footprint "eagle-import:R0603")
      (libsource (lib "eagle-import") (part "R-EU_R0603"))
    )
    (comp (ref "L1111")
      (value "4.7uH")
      (footprint "eagle-import:L5650M")
      (libsource (lib "eagle-import") (part "L-EUL5650M"))
    )
    (comp (ref "R1111")
      (value "4.02kR")
      (footprint "eagle-import:R0603")
      (libsource (lib "eagle-import") (part "R-EU_R0603"))
    )
    (comp (ref "R1112")
      (value "6.04kR")
      (footprint "eagle-import:R0603")
      (libsource (lib "eagle-import") (part "R-EU_R0603"))
    )
    (comp (ref "R1113")
      (value "100kR")
      (footprint "eagle-import:R0603")
      (libsource (lib "eagle-import") (part "R-EU_R0603"))
    )
    (comp (ref "R1114")
      (value "15kR")
      (footprint "eagle-import:R0603")
      (libsource (lib "eagle-import") (part "R-EU_R0603"))
    )
    (comp (ref "R1115")
      (value "68kR")
      (footprint "eagle-import:R0603")
      (libsource (lib "eagle-import") (part "R-EU_R0603"))
    )
    (comp (ref "R1131")
      (value "4.02kR")
      (footprint "eagle-import:R0603")
      (libsource (lib "eagle-import") (part "R-EU_R0603"))
    )
    (comp (ref "R1132")
      (value "6.04kR")
      (footprint "eagle-import:R0603")
      (libsource (lib "eagle-import") (part "R-EU_R0603"))
    )
    (comp (ref "R1141")
      (value "100pF")
      (footprint "eagle-import:R0603")
      (libsource (lib "eagle-import") (part "R-EU_R0603"))
    )
    (comp (ref "R1142")
      (value "2.0kR")
      (footprint "eagle-import:R0603")
      (libsource (lib "eagle-import") (part "R-EU_R0603"))
    )
    (comp (ref "U1111")
      (value "LM2831YMF")
      (footprint "eagle-import:SOT95P280X145-5N")
      (fields (field (name "MPN") "LM2831YMF/NOPB"))
      (libsource (lib "eagle-import") (part "LM2831YMF"))
    )
    (comp (ref "U1121")
      (value "LM4120IM5-3.0")
      (footprint "eagle-import:SOT95P285X120-5N")
      (libsource (lib "eagle-import") (part "LM4120IM5-3.0"))
    )
    (comp (ref "C201")
      (value "100pF")
      (footprint "eagle-import:C0603")
      (libsource (lib "eagle-import") (part "C-EUC0603"))
    )
    (comp (ref "C251")
      (value "100pF")
      (footprint "eagle-import:C0603")
      (libsource (lib "eagle-import") (part "C-EUC0603"))
    )
    (comp (ref "C271")
      (value "0pF")
      (footprint "eagle-import:C0603")
      (libsource (lib "eagle-import") (part "C-EUC0603"))
    )
    (comp (ref "C272")
      (value "0pF")
      (footprint "eagle-import:C0603")
      (libsource (lib "eagle-import") (part "C-EUC0603"))
    )
    (comp (ref "C281")
      (value "0pF")
      (footprint "eagle-import:C0603")
      (libsource (lib "eagle-import") (part "C-EUC0603"))
    )
    (comp (ref "C282")
      (value "0pF")
      (footprint "eagle-import:C0603")
      (libsource (lib "eagle-import") (part "C-EUC0603"))
    )
    (comp (ref "C291")
      (value "0pF")
      (footprint "eagle-import:C0603")
      (libsource (lib "eagle-import") (part "C-EUC0603"))
    )
    (comp (ref "C292")
      (value "0pF")
      (footprint "eagle-import:C0603")
      (libsource (lib "eagle-import") (part "C-EUC0603"))
    )
    (comp (ref "D201")
      (value "BZX84-5V1")
      (footprint "eagle-import:TO236")
      (libsource (lib "eagle-import") (part "BZX84CSMD"))
    )
    (comp (ref "JP201")
      (value "POW")
      (footprint "eagle-import:1X02")
      (libsource (lib "eagle-import") (part "HEADER-1X2"))
    )
    (comp (ref "L291")
      (value "WE-CBF_300R")
      (footprint "eagle-import:L3216C")
      (libsource (lib "eagle-import") (part "L-EUL3216C"))
    )
    (comp (ref "R211")
      (value "10kR")
      (footprint "eagle-import:R0603")
      (libsource (lib "eagle-import") (part "R-EU_R0603"))
    )
    (comp (ref "R212")
      (value "10kR")
      (footprint "eagle-import:R0603")
      (libsource (lib "eagle-import") (part "R-EU_R0603"))
    )
    (comp (ref "R221")
      (value "68R")
      (footprint "eagle-import:R0603")
      (libsource (lib "eagle-import") (part "R-EU_R0603"))
    )
    (comp (ref "R222")
      (value "68R")
      (footprint "eagle-import:R0603")
      (libsource (lib "eagle-import") (part "R-EU_R0603"))
    )
    (comp (ref "R223")
      (value "68R")
      (footprint "eagle-import:R0603")
      (libsource (lib "eagle-import") (part "R-EU_R0603"))
    )
    (comp (ref "R224")
      (value "68R")
      (footprint "eagle-import:R0603")
      (libsource (lib "eagle-import") (part "R-EU_R0603"))
    )
    (comp (ref "R231")
      (value "68R")
      (footprint "eagle-import:R0603")
      (libsource (lib "eagle-import") (part "R-EU_R0603"))
    )
    (comp (ref "R232")
      (value "68R")
      (footprint "eagle-import:R0603")
      (libsource (lib "eagle-import") (part "R-EU_R0603"))
    )
    (comp (ref "R233")
      (value "68R")
      (footprint "eagle-import:R0603")
      (libsource (lib "eagle-import") (part "R-EU_R0603"))
    )
    (comp (ref "R234")
      (value "68R")
      (footprint "eagle-import:R0603")
      (libsource (lib "eagle-import") (part "R-EU_R0603"))
    )
    (comp (ref "R241")
      (value "68R")
      (footprint "eagle-import:R0603")
      (libsource (lib "eagle-import") (part "R-EU_R0603"))
    )
    (comp (ref "R251")
      (value "68R")
      (footprint "eagle-import:R0603")
      (libsource (lib "eagle-import") (part "R-EU_R0603"))
    )
    (comp (ref "R271")
      (value "0R")
      (footprint "eagle-import:R0805")
      (libsource (lib "eagle-import") (part "R-EU_R0805"))
    )
    (comp (ref "R281")
      (value "0R")
      (footprint "eagle-import:R0805")
      (libsource (lib "eagle-import") (part "R-EU_R0805"))
    )
    (comp (ref "R291")
      (value "0R")
      (footprint "eagle-import:R0603")
      (libsource (lib "eagle-import") (part "R-EU_R0603"))
    )
    (comp (ref "RPOLY291")
      (value "50mA/150mA")
      (footprint "eagle-import:R1210")
      (libsource (lib "eagle-import") (part "R-EU_R1210"))
    )
    (comp (ref "U201")
      (value "SIM808")
      (footprint "eagle-import:SIM808")
      (libsource (lib "eagle-import") (part "SIM808"))
    )
    (comp (ref "X291")
      (value "MCX-J-P-X-RA-SM1")
      (footprint "eagle-import:MCX-J-P-X-RA-SM1")
      (libsource (lib "eagle-import") (part "MCX-J-P-X-RA-SM1"))
    )
    (comp (ref "C601")
      (value "100nF")
      (footprint "eagle-import:C0603")
      (libsource (lib "eagle-import") (part "C-EUC0603"))
    )
    (comp (ref "C611")
      (value "100nF")
      (footprint "eagle-import:C0603")
      (libsource (lib "eagle-import") (part "C-EUC0603"))
    )
    (comp (ref "C612")
      (value "100nF")
      (footprint "eagle-import:C0603")
      (libsource (lib "eagle-import") (part "C-EUC0603"))
    )
    (comp (ref "C681")
      (value "82pF")
      (footprint "eagle-import:C0603")
      (libsource (lib "eagle-import") (part "C-EUC0603"))
    )
    (comp (ref "C686")
      (value "150pF")
      (footprint "eagle-import:C0603")
      (libsource (lib "eagle-import") (part "C-EUC0603"))
    )
    (comp (ref "L671")
      (value "22nH")
      (footprint "eagle-import:R0603")
      (libsource (lib "eagle-import") (part "R-EU_R0603"))
    )
    (comp (ref "L681")
      (value "100nH")
      (footprint "eagle-import:R0603")
      (libsource (lib "eagle-import") (part "R-EU_R0603"))
    )
    (comp (ref "L682")
      (value "56nH")
      (footprint "eagle-import:R0603")
      (libsource (lib "eagle-import") (part "R-EU_R0603"))
    )
    (comp (ref "L686")
      (value "33nH")
      (footprint "eagle-import:R0603")
      (libsource (lib "eagle-import") (part "R-EU_R0603"))
    )
    (comp (ref "Q651")
      (value "ABM3B-16MHZ-10-R50-1-U")
      (footprint "eagle-import:ABM03B")
      (libsource (lib "eagle-import") (part "ABM03B-16.000MHZ"))
    )
    (comp (ref "U601")
      (value "AX5243")
      (footprint "eagle-import:QFN20-4X4-0P5-PAD")
      (libsource (lib "eagle-import") (part "AX5243"))
    )
    (comp (ref "X685")
      (value "SMA_CON")
      (footprint "eagle-import:SMA_SMT_AMPHENOL_901-143")
      (fields (field (name "MPN") "901-143"))
      (libsource (lib "eagle-import") (part "SMA_SMT_AMPHENOL-901-143"))
    )
    (comp (ref "C401")
      (value "100nF")
      (footprint "eagle-import:C0603")
      (libsource (lib "eagle-import") (part "C-EUC0603"))
    )
    (comp (ref "R401")
      (value "10kR")
      (footprint "eagle-import:R0603")
      (libsource (lib "eagle-import") (part "R-EU_R0603"))
    )
    (comp (ref "R402")
      (value "10kR")
      (footprint "eagle-import:R0603")
      (libsource (lib "eagle-import") (part "R-EU_R0603"))
    )
    (comp (ref "U401")
      (value "MS5607-02BA03")
      (footprint "eagle-import:MS5607-02BA")
      (libsource (lib "eagle-import") (part "MS5607-02BA03"))
    )
    (comp (ref "C701")
      (value "1nF")
      (footprint "eagle-import:C0603")
      (libsource (lib "eagle-import") (part "C-EUC0603"))
    )
    (comp (ref "C711")
      (value "100nF")
      (footprint "eagle-import:C0603")
      (libsource (lib "eagle-import") (part "C-EUC0603"))
    )
    (comp (ref "C712")
      (value "47uF")
      (footprint "eagle-import:C0805")
      (libsource (lib "eagle-import") (part "C-EUC0805"))
    )
    (comp (ref "D721")
      (value "BZX84-3V6")
      (footprint "eagle-import:TO236")
      (libsource (lib "eagle-import") (part "BZX84CSMD"))
    )
    (comp (ref "D722")
      (value "BZX84-3V6")
      (footprint "eagle-import:TO236")
      (libsource (lib "eagle-import") (part "BZX84CSMD"))
    )
    (comp (ref "R701")
      (value "330kR")
      (footprint "eagle-import:R0603")
      (libsource (lib "eagle-import") (part "R-EU_R0603"))
    )
    (comp (ref "R721")
      (value "1.5kR")
      (footprint "eagle-import:R0603")
      (libsource (lib "eagle-import") (part "R-EU_R0603"))
    )
    (comp (ref "R722")
      (value "68R")
      (footprint "eagle-import:R0603")
      (libsource (lib "eagle-import") (part "R-EU_R0603"))
    )
    (comp (ref "R723")
      (value "68R")
      (footprint "eagle-import:R0603")
      (libsource (lib "eagle-import") (part "R-EU_R0603"))
    )
    (comp (ref "R724")
      (value "1MR")
      (footprint "eagle-import:R0603")
      (libsource (lib "eagle-import") (part "R-EU_R0603"))
    )
    (comp (ref "R725")
      (value "68R")
      (footprint "eagle-import:R0603")
      (libsource (lib "eagle-import") (part "R-EU_R0603"))
    )
    (comp (ref "RPOLY711")
      (value "1.1A/2.2A")
      (footprint "eagle-import:M1206")
      (libsource (lib "eagle-import") (part "R-EU_M1206"))
    )
    (comp (ref "X701")
      (value "MOLEX_105017-0001")
      (footprint "eagle-import:USB-B-MICRO-SMD_MOLEX-105017-0001")
      (libsource (lib "eagle-import") (part "USB_MICRO-B_MOLEX"))
    )
    (comp (ref "FM1201")
      (value "FIDUCIAL_MARK_1MM")
      (footprint "eagle-import:FIDUCIAL_MARK_1MM")
      (libsource (lib "eagle-import") (part "FIDUCIAL_MARK_1MM"))
    )
    (comp (ref "FM1202")
      (value "FIDUCIAL_MARK_1MM")
      (footprint "eagle-import:FIDUCIAL_MARK_1MM")
      (libsource (lib "eagle-import") (part "FIDUCIAL_MARK_1MM"))
    )
    (comp (ref "FM1203")
      (value "FIDUCIAL_MARK_1MM")
      (footprint "eagle-import:FIDUCIAL_MARK_1MM")
      (libsource (lib "eagle-import") (part "FIDUCIAL_MARK_1MM"))
    )
    (comp (ref "FM1204")
      (value "FIDUCIAL_MARK_1MM")
      (footprint "eagle-import:FIDUCIAL_MARK_1MM")
      (libsource (lib "eagle-import") (part "FIDUCIAL_MARK_1MM"))
    )
    (comp (ref "H1201")
      (value "MOUNT-PAD-ROUND2.8")
      (footprint "eagle-import:2,8-PAD")
      (libsource (lib "eagle-import") (part "MOUNT-PAD-ROUND2.8"))
    )
    (comp (ref "H1203")
      (value "MOUNT-PAD-ROUND2.8")
      (footprint "eagle-import:2,8-PAD")
      (libsource (lib "eagle-import") (part "MOUNT-PAD-ROUND2.8"))
    )
    (comp (ref "H1204")
      (value "MOUNT-PAD-ROUND2.8")
      (footprint "eagle-import:2,8-PAD")
      (libsource (lib "eagle-import") (part "MOUNT-PAD-ROUND2.8"))
    )
    (comp (ref "C501")
      (value "100nF")
      (footprint "eagle-import:C0603")
      (libsource (lib "eagle-import") (part "C-EUC0603"))
    )
    (comp (ref "U501")
      (value "SHT31-DIS")
      (footprint "eagle-import:DFN8_SHT")
      (libsource (lib "eagle-import") (part "SHT31-DIS"))
    )
    (comp (ref "X801")
      (value "MICROSIM-8P_SDCARD-8P_MOLEX-104642-1610")
      (footprint "eagle-import:MICROSIM-8P_SDCARD-8P_MOLEX-104642-1610")
      (fields (field (name "MPN") "MOLEX-104642-1610"))
      (libsource (lib "eagle-import") (part "MICROSIM-8P_SDCARD-8P_MOLEX-104642-1610"))
    )
    (comp (ref "C301")
      (value "100nF")
      (footprint "eagle-import:C0603")
      (libsource (lib "eagle-import") (part "C-EUC0603"))
    )
    (comp (ref "C302")
      (value "100nF")
      (footprint "eagle-import:C0603")
      (libsource (lib "eagle-import") (part "C-EUC0603"))
    )
    (comp (ref "R301")
      (value "68R")
      (footprint "eagle-import:R0603")
      (libsource (lib "eagle-import") (part "R-EU_R0603"))
    )
    (comp (ref "U301")
      (value "MPU-9250")
      (footprint "eagle-import:QFN24-3X3")
      (libsource (lib "eagle-import") (part "MPU-9250"))
    )
  )
  (nets
    (net (code "1") (name "+3V0") (class "Default")
      (node (ref "C1002") (pin "1") (pinfunction "1_1") (pintype "passive"))
      (node (ref "C101") (pin "1") (pinfunction "1_1") (pintype "passive"))
      (node (ref "C251") (pin "1") (pinfunction "1_1") (pintype "passive"))
      (node (ref "R1142") (pin "2") (pinfunction "2_2") (pintype "passive"))
      (node (ref "U1001") (pin "4") (pinfunction "VCC_3V0_4") (pintype "power_in"))
      (node (ref "U101") (pin "51") (pinfunction "VBAT_51") (pintype "power_in"))
      (node (ref "U1121") (pin "5") (pinfunction "VOUT_5") (pintype "power_in"))
      (node (ref "U201") (pin "17") (pinfunction "VRTC_17") (pintype "power_in"))
    )
    (net (code "2") (name "+3V3") (class "Default")
      (node (ref "C1012") (pin "1") (pinfunction "1_1") (pintype "passive"))
      (node (ref "C1112") (pin "1") (pinfunction "1_1") (pintype "passive"))
      (node (ref "C1113") (pin "1") (pinfunction "1_1") (pintype "passive"))
      (node (ref "C191") (pin "1") (pinfunction "1_1") (pintype "passive"))
      (node (ref "C192") (pin "1") (pinfunction "1_1") (pintype "passive"))
      (node (ref "C193") (pin "1") (pinfunction "1_1") (pintype "passive"))
      (node (ref "C194") (pin "1") (pinfunction "1_1") (pintype "passive"))
      (node (ref "C195") (pin "1") (pinfunction "1_1") (pintype "passive"))
      (node (ref "C301") (pin "1") (pinfunction "1_1") (pintype "passive"))
      (node (ref "C401") (pin "1") (pinfunction "1_1") (pintype "passive"))
      (node (ref "C501") (pin "1") (pinfunction "1_1") (pintype "passive"))
      (node (ref "C601") (pin "1") (pinfunction "1_1") (pintype "passive"))
      (node (ref "L1111") (pin "1") (pinfunction "1_1") (pintype "passive"))
      (node (ref "L191") (pin "2") (pinfunction "2_2") (pintype "passive"))
      (node (ref "R1012") (pin "2") (pinfunction "2_2") (pintype "passive"))
      (node (ref "R111") (pin "2") (pinfunction "2_2") (pintype "passive"))
      (node (ref "R1115") (pin "2") (pinfunction "2_2") (pintype "passive"))
      (node (ref "R112") (pin "2") (pinfunction "2_2") (pintype "passive"))
      (node (ref "R211") (pin "1") (pinfunction "1_1") (pintype "passive"))
      (node (ref "R212") (pin "1") (pinfunction "1_1") (pintype "passive"))
      (node (ref "R401") (pin "2") (pinfunction "2_2") (pintype "passive"))
      (node (ref "R402") (pin "2") (pinfunction "2_2") (pintype "passive"))
      (node (ref "RPOLY291") (pin "2") (pinfunction "2_2") (pintype "passive"))
      (node (ref "U101") (pin "15") (pinfunction "VCC_1_15") (pintype "power_in"))
      (node (ref "U101") (pin "25") (pinfunction "VCC_2_25") (pintype "power_in"))
      (node (ref "U101") (pin "35") (pinfunction "VCC_3_35") (pintype "power_in"))
      (node (ref "U101") (pin "45") (pinfunction "VCC_4_45") (pintype "power_in"))
      (node (ref "U101") (pin "53") (pinfunction "VCC_5_53") (pintype "power_in"))
      (node (ref "U1011") (pin "5") (pinfunction "V+_5") (pintype "power_in"))
      (node (ref "U1021") (pin "5") (pinfunction "V+_5") (pintype "power_in"))
      (node (ref "U301") (pin "1") (pinfunction "VDDIO_1") (pintype "power_in"))
      (node (ref "U301") (pin "13") (pinfunction "VDD_13") (pintype "power_in"))
      (node (ref "U301") (pin "22") (pinfunction "~{CS}_22") (pintype "input"))
      (node (ref "U301") (pin "8") (pinfunction "VDDIO_8") (pintype "power_in"))
      (node (ref "U401") (pin "1") (pinfunction "VDD_1") (pintype "power_in"))
      (node (ref "U401") (pin "2") (pinfunction "PS_2") (pintype "input"))
      (node (ref "U401") (pin "4") (pinfunction "CSB_~{ADDR}_4") (pintype "input"))
      (node (ref "U501") (pin "5") (pinfunction "VDD_5") (pintype "power_in"))
      (node (ref "U601") (pin "16") (pinfunction "VDD_IO_16") (pintype "power_in"))
      (node (ref "X111") (pin "7") (pinfunction "7_7") (pintype "passive"))
      (node (ref "X121") (pin "5") (pinfunction "5_5") (pintype "passive"))
      (node (ref "X131") (pin "2") (pinfunction "2_2") (pintype "passive"))
    )
    (net (code "3") (name "+5V") (class "Default")
      (node (ref "C711") (pin "1") (pinfunction "1_1") (pintype "passive"))
      (node (ref "C712") (pin "1") (pinfunction "1_1") (pintype "passive"))
      (node (ref "D1121") (pin "A") (pinfunction "A_A") (pintype "passive"))
      (node (ref "JP201") (pin "1") (pinfunction "1_1") (pintype "passive"))
      (node (ref "R1112") (pin "2") (pinfunction "2_2") (pintype "passive"))
      (node (ref "RPOLY711") (pin "2") (pinfunction "2_2") (pintype "passive"))
      (node (ref "X121") (pin "3") (pinfunction "3_3") (pintype "passive"))
    )
    (net (code "4") (name "AD_3V0") (class "Default")
      (node (ref "R1141") (pin "2") (pinfunction "2_2") (pintype "passive"))
      (node (ref "R1142") (pin "1") (pinfunction "1_1") (pintype "passive"))
      (node (ref "U101") (pin "62") (pinfunction "PA0_62") (pintype "bidirectional"))
    )
    (net (code "5") (name "AD_5V0") (class "Default")
      (node (ref "R1111") (pin "2") (pinfunction "2_2") (pintype "passive"))
      (node (ref "R1112") (pin "1") (pinfunction "1_1") (pintype "passive"))
      (node (ref "U101") (pin "64") (pinfunction "PA2_64") (pintype "bidirectional"))
    )
    (net (code "6") (name "AD_VBAT") (class "Default")
      (node (ref "R1131") (pin "1") (pinfunction "1_1") (pintype "passive"))
      (node (ref "R1132") (pin "2") (pinfunction "2_2") (pintype "passive"))
      (node (ref "U101") (pin "1") (pinfunction "PA3_1") (pintype "bidirectional"))
    )
    (net (code "7") (name "AD_VCTCXO") (class "Default")
      (node (ref "R1021") (pin "2") (pinfunction "2_2") (pintype "passive"))
      (node (ref "U101") (pin "63") (pinfunction "PA1_63") (pintype "bidirectional"))
      (node (ref "U1021") (pin "1") (pinfunction "OUT_1") (pintype "output"))
    )
    (net (code "8") (name "AVCC") (class "Default")
      (node (ref "C196") (pin "1") (pinfunction "1_1") (pintype "passive"))
      (node (ref "L191") (pin "1") (pinfunction "1_1") (pintype "passive"))
      (node (ref "U101") (pin "61") (pinfunction "AVCC_61") (pintype "power_in"))
    )
    (net (code "9") (name "AX_ANT") (class "Default")
      (node (ref "C686") (pin "2") (pinfunction "2_2") (pintype "passive"))
      (node (ref "L682") (pin "2") (pinfunction "2_2") (pintype "passive"))
      (node (ref "X685") (pin "1") (pinfunction "1_1") (pintype "passive"))
    )
    (net (code "10") (name "AX_ANTN") (class "Default")
      (node (ref "C686") (pin "1") (pinfunction "1_1") (pintype "passive"))
      (node (ref "L686") (pin "2") (pinfunction "2_2") (pintype "passive"))
      (node (ref "U601") (pin "4") (pinfunction "ANTN_4") (pintype "passive"))
    )
    (net (code "11") (name "AX_ANTP") (class "Default")
      (node (ref "C681") (pin "1") (pinfunction "1_1") (pintype "passive"))
      (node (ref "L681") (pin "1") (pinfunction "1_1") (pintype "passive"))
      (node (ref "U601") (pin "3") (pinfunction "ANTP_3") (pintype "passive"))
    )
    (net (code "12") (name "AX_ANT_I") (class "Default")
      (node (ref "C681") (pin "2") (pinfunction "2_2") (pintype "passive"))
      (node (ref "L682") (pin "1") (pinfunction "1_1") (pintype "passive"))
    )
    (net (code "13") (name "AX_CLK") (class "Default")
      (node (ref "U101") (pin "23") (pinfunction "PC7_23") (pintype "bidirectional"))
      (node (ref "U601") (pin "11") (pinfunction "CLK_11") (pintype "input"))
    )
    (net (code "14") (name "AX_IRQ") (class "Default")
      (node (ref "U101") (pin "19") (pinfunction "PC3_19") (pintype "bidirectional"))
      (node (ref "U601") (pin "14") (pinfunction "IRQ_14") (pintype "bidirectional"))
    )
    (net (code "15") (name "AX_L1") (class "Default")
      (node (ref "L671") (pin "1") (pinfunction "1_1") (pintype "passive"))
      (node (ref "U601") (pin "8") (pinfunction "L1_8") (pintype "passive"))
    )
    (net (code "16") (name "AX_L2") (class "Default")
      (node (ref "L671") (pin "2") (pinfunction "2_2") (pintype "passive"))
      (node (ref "U601") (pin "7") (pinfunction "L2_7") (pintype "passive"))
    )
    (net (code "17") (name "AX_MISO") (class "Default")
      (node (ref "U101") (pin "22") (pinfunction "PC6_22") (pintype "bidirectional"))
      (node (ref "U601") (pin "12") (pinfunction "MISO_12") (pintype "output"))
    )
    (net (code "18") (name "AX_MOSI") (class "Default")
      (node (ref "U101") (pin "21") (pinfunction "PC5_21") (pintype "bidirectional"))
      (node (ref "U601") (pin "13") (pinfunction "MOSI_13") (pintype "input"))
    )
    (net (code "19") (name "AX_SEL") (class "Default")
      (node (ref "U101") (pin "20") (pinfunction "PC4_20") (pintype "bidirectional"))
      (node (ref "U601") (pin "10") (pinfunction "SEL_10") (pintype "input"))
    )
    (net (code "20") (name "BT_ANT") (class "Default")
      (node (ref "C282") (pin "1") (pinfunction "1_1") (pintype "passive"))
      (node (ref "R281") (pin "2") (pinfunction "2_2") (pintype "passive"))
    )
    (net (code "21") (name "BT_RF") (class "Default")
      (node (ref "C281") (pin "1") (pinfunction "1_1") (pintype "passive"))
      (node (ref "R281") (pin "1") (pinfunction "1_1") (pintype "passive"))
      (node (ref "U201") (pin "53") (pinfunction "ANT_BT_53") (pintype "bidirectional"))
    )
    (net (code "22") (name "CTS1") (class "Default")
      (node (ref "R173") (pin "1") (pinfunction "1_1") (pintype "passive"))
      (node (ref "U101") (pin "55") (pinfunction "PF7_55") (pintype "bidirectional"))
    )
    (net (code "23") (name "DCD1") (class "Default")
      (node (ref "R171") (pin "1") (pinfunction "1_1") (pintype "passive"))
      (node (ref "U101") (pin "47") (pinfunction "PF1_47") (pintype "bidirectional"))
    )
    (net (code "24") (name "DTR1") (class "Default")
      (node (ref "R222") (pin "1") (pinfunction "1_1") (pintype "passive"))
      (node (ref "U101") (pin "46") (pinfunction "PF0_46") (pintype "bidirectional"))
    )
    (net (code "25") (name "EN") (class "Default")
      (node (ref "R1113") (pin "2") (pinfunction "2_2") (pintype "passive"))
      (node (ref "U1111") (pin "4") (pinfunction "EN_4") (pintype "input"))
    )
    (net (code "26") (name "FB") (class "Default")
      (node (ref "R1114") (pin "2") (pinfunction "2_2") (pintype "passive"))
      (node (ref "R1115") (pin "1") (pinfunction "1_1") (pintype "passive"))
      (node (ref "U1111") (pin "3") (pinfunction "FB_3") (pintype "input"))
    )
    (net (code "27") (name "GND") (class "Default")
      (node (ref "C1001") (pin "2") (pinfunction "2_2") (pintype "passive"))
      (node (ref "C1002") (pin "2") (pinfunction "2_2") (pintype "passive"))
      (node (ref "C101") (pin "2") (pinfunction "2_2") (pintype "passive"))
      (node (ref "C1011") (pin "2") (pinfunction "2_2") (pintype "passive"))
      (node (ref "C1012") (pin "2") (pinfunction "2_2") (pintype "passive"))
      (node (ref "C1111") (pin "2") (pinfunction "2_2") (pintype "passive"))
      (node (ref "C1112") (pin "2") (pinfunction "2_2") (pintype "passive"))
      (node (ref "C1113") (pin "2") (pinfunction "2_2") (pintype "passive"))
      (node (ref "C1121") (pin "2") (pinfunction "2_2") (pintype "passive"))
      (node (ref "C141") (pin "2") (pinfunction "2_2") (pintype "passive"))
      (node (ref "C191") (pin "2") (pinfunction "2_2") (pintype "passive"))
      (node (ref "C192") (pin "2") (pinfunction "2_2") (pintype "passive"))
      (node (ref "C193") (pin "2") (pinfunction "2_2") (pintype "passive"))
      (node (ref "C194") (pin "2") (pinfunction "2_2") (pintype "passive"))
      (node (ref "C195") (pin "2") (pinfunction "2_2") (pintype "passive"))
      (node (ref "C196") (pin "2") (pinfunction "2_2") (pintype "passive"))
      (node (ref "C201") (pin "2") (pinfunction "2_2") (pintype "passive"))
      (node (ref "C251") (pin "2") (pinfunction "2_2") (pintype "passive"))
      (node (ref "C271") (pin "2") (pinfunction "2_2") (pintype "passive"))
      (node (ref "C272") (pin "2") (pinfunction "2_2") (pintype "passive"))
      (node (ref "C281") (pin "2") (pinfunction "2_2") (pintype "passive"))
      (node (ref "C282") (pin "2") (pinfunction "2_2") (pintype "passive"))
      (node (ref "C291") (pin "2") (pinfunction "2_2") (pintype "passive"))
      (node (ref "C292") (pin "2") (pinfunction "2_2") (pintype "passive"))
      (node (ref "C301") (pin "2") (pinfunction "2_2") (pintype "passive"))
      (node (ref "C302") (pin "2") (pinfunction "2_2") (pintype "passive"))
      (node (ref "C401") (pin "2") (pinfunction "2_2") (pintype "passive"))
      (node (ref "C501") (pin "2") (pinfunction "2_2") (pintype "passive"))
      (node (ref "C601") (pin "2") (pinfunction "2_2") (pintype "passive"))
      (node (ref "C611") (pin "2") (pinfunction "2_2") (pintype "passive"))
      (node (ref "C612") (pin "2") (pinfunction "2_2") (pintype "passive"))
      (node (ref "C701") (pin "2") (pinfunction "2_2") (pintype "passive"))
      (node (ref "C711") (pin "2") (pinfunction "2_2") (pintype "passive"))
      (node (ref "C712") (pin "2") (pinfunction "2_2") (pintype "passive"))
      (node (ref "C901") (pin "2") (pinfunction "2_2") (pintype "passive"))
      (node (ref "D1111") (pin "A") (pinfunction "A_A") (pintype "passive"))
      (node (ref "D201") (pin "A") (pinfunction "A_A") (pintype "passive"))
      (node (ref "D721") (pin "A") (pinfunction "A_A") (pintype "passive"))
      (node (ref "D722") (pin "A") (pinfunction "A_A") (pintype "passive"))
      (node (ref "H1201") (pin "B2,8") (pinfunction "MOUNT_B2,8") (pintype "passive"))
      (node (ref "H1203") (pin "B2,8") (pinfunction "MOUNT_B2,8") (pintype "passive"))
      (node (ref "H1204") (pin "B2,8") (pinfunction "MOUNT_B2,8") (pintype "passive"))
      (node (ref "L681") (pin "2") (pinfunction "2_2") (pintype "passive"))
      (node (ref "L686") (pin "1") (pinfunction "1_1") (pintype "passive"))
      (node (ref "Q651") (pin "2") (pinfunction "3_2") (pintype "passive"))
      (node (ref "Q651") (pin "4") (pinfunction "3_4") (pintype "passive"))
      (node (ref "R1011") (pin "1") (pinfunction "1_1") (pintype "passive"))
      (node (ref "R1111") (pin "1") (pinfunction "1_1") (pintype "passive"))
      (node (ref "R1114") (pin "1") (pinfunction "1_1") (pintype "passive"))
      (node (ref "R1131") (pin "2") (pinfunction "2_2") (pintype "passive"))
      (node (ref "R1141") (pin "1") (pinfunction "1_1") (pintype "passive"))
      (node (ref "R701") (pin "2") (pinfunction "2_2") (pintype "passive"))
      (node (ref "R724") (pin "2") (pinfunction "2_2") (pintype "passive"))
      (node (ref "U1001") (pin "2") (pinfunction "GND_2") (pintype "power_in"))
      (node (ref "U101") (pin "14") (pinfunction "GND_1_14") (pintype "passive"))
      (node (ref "U101") (pin "24") (pinfunction "GND_2_24") (pintype "passive"))
      (node (ref "U101") (pin "34") (pinfunction "GND_3_34") (pintype "passive"))
      (node (ref "U101") (pin "44") (pinfunction "GND_4_44") (pintype "passive"))
      (node (ref "U101") (pin "52") (pinfunction "GND_5_52") (pintype "passive"))
      (node (ref "U101") (pin "60") (pinfunction "GND_6_60") (pintype "passive"))
      (node (ref "U1011") (pin "2") (pinfunction "V-_2") (pintype "power_in"))
      (node (ref "U1021") (pin "2") (pinfunction "V-_2") (pintype "power_in"))
      (node (ref "U1111") (pin "2") (pinfunction "GND_2") (pintype "passive"))
      (node (ref "U1121") (pin "2") (pinfunction "GND_2") (pintype "passive"))
      (node (ref "U201") (pin "1") (pinfunction "GND_1") (pintype "power_in"))
      (node (ref "U201") (pin "18") (pinfunction "GND_18") (pintype "power_in"))
      (node (ref "U201") (pin "2") (pinfunction "GND_2") (pintype "power_in"))
      (node (ref "U201") (pin "28") (pinfunction "GND_28") (pintype "power_in"))
      (node (ref "U201") (pin "3") (pinfunction "GND_3") (pintype "power_in"))
      (node (ref "U201") (pin "34") (pinfunction "GND_34") (pintype "power_in"))
      (node (ref "U201") (pin "36") (pinfunction "GND_36") (pintype "power_in"))
      (node (ref "U201") (pin "40") (pinfunction "GND_40") (pintype "power_in"))
      (node (ref "U201") (pin "51") (pinfunction "GND_51") (pintype "power_in"))
      (node (ref "U201") (pin "52") (pinfunction "GND_52") (pintype "power_in"))
      (node (ref "U201") (pin "54") (pinfunction "GND_54") (pintype "power_in"))
      (node (ref "U201") (pin "64") (pinfunction "GND_64") (pintype "power_in"))
      (node (ref "U201") (pin "65") (pinfunction "GND_65") (pintype "power_in"))
      (node (ref "U201") (pin "67") (pinfunction "GND_67") (pintype "power_in"))
      (node (ref "U201") (pin "68") (pinfunction "GND_68") (pintype "power_in"))
      (node (ref "U301") (pin "11") (pinfunction "FSYNC_11") (pintype "passive"))
      (node (ref "U301") (pin "18") (pinfunction "GND_18") (pintype "passive"))
      (node (ref "U301") (pin "20") (pinfunction "GND_20") (pintype "passive"))
      (node (ref "U301") (pin "9") (pinfunction "AD0/SDO_9") (pintype "bidirectional"))
      (node (ref "U401") (pin "3") (pinfunction "GND_3") (pintype "passive"))
      (node (ref "U501") (pin "2") (pinfunction "ADDR_2") (pintype "input"))
      (node (ref "U501") (pin "6") (pinfunction "~{RESET}_6") (pintype "passive"))
      (node (ref "U501") (pin "7") (pinfunction "R_7") (pintype "passive"))
      (node (ref "U501") (pin "8") (pinfunction "VSS_8") (pintype "passive"))
      (node (ref "U501") (pin "9") (pinfunction "PAD_9") (pintype "passive"))
      (node (ref "U601") (pin "17") (pinfunction "GPADC1_17") (pintype "passive"))
      (node (ref "U601") (pin "18") (pinfunction "GPADC2_18") (pintype "passive"))
      (node (ref "U601") (pin "2") (pinfunction "GND_2") (pintype "power_in"))
      (node (ref "U601") (pin "21") (pinfunction "GND_21") (pintype "power_in"))
      (node (ref "X111") (pin "10") (pinfunction "10_10") (pintype "passive"))
      (node (ref "X111") (pin "2") (pinfunction "2_2") (pintype "passive"))
      (node (ref "X121") (pin "1") (pinfunction "1_1") (pintype "passive"))
      (node (ref "X121") (pin "6") (pinfunction "6_6") (pintype "passive"))
      (node (ref "X131") (pin "6") (pinfunction "6_6") (pintype "passive"))
      (node (ref "X181") (pin "1") (pinfunction "1_1") (pintype "passive"))
      (node (ref "X291") (pin "2") (pinfunction "2_2") (pintype "passive"))
      (node (ref "X291") (pin "3") (pinfunction "3_3") (pintype "passive"))
      (node (ref "X291") (pin "4") (pinfunction "4_4") (pintype "passive"))
      (node (ref "X291") (pin "5") (pinfunction "5_5") (pintype "passive"))
      (node (ref "X685") (pin "2") (pinfunction "2_2") (pintype "passive"))
      (node (ref "X685") (pin "3") (pinfunction "2_3") (pintype "passive"))
      (node (ref "X685") (pin "4") (pinfunction "2_4") (pintype "passive"))
      (node (ref "X685") (pin "5") (pinfunction "2_5") (pintype "passive"))
      (node (ref "X701") (pin "GND") (pinfunction "GND_GND") (pintype "passive"))
      (node (ref "X801") (pin "G1") (pinfunction "SHIELD_G1") (pintype "passive"))
      (node (ref "X801") (pin "G2") (pinfunction "SHIELD_G2") (pintype "passive"))
      (node (ref "X801") (pin "G3") (pinfunction "SHIELD_G3") (pintype "passive"))
      (node (ref "X801") (pin "G4") (pinfunction "SHIELD_G4") (pintype "passive"))
      (node (ref "X801") (pin "G5") (pinfunction "SHIELD_G5") (pintype "passive"))
      (node (ref "X801") (pin "G6") (pinfunction "SHIELD_G6") (pintype "passive"))
      (node (ref "X801") (pin "G7") (pinfunction "SHIELD_G7") (pintype "passive"))
      (node (ref "X801") (pin "G8") (pinfunction "SHIELD_G8") (pintype "passive"))
      (node (ref "X801") (pin "S5") (pinfunction "S5_S5") (pintype "passive"))
      (node (ref "X801") (pin "T6") (pinfunction "T6_T6") (pintype "passive"))
      (node (ref "X901") (pin "3") (pinfunction "3_3") (pintype "passive"))
    )
    (net (code "28") (name "GPS_1PPS") (class "Default")
      (node (ref "R251") (pin "1") (pinfunction "1_1") (pintype "passive"))
      (node (ref "U101") (pin "58") (pinfunction "PR0_58") (pintype "bidirectional"))
    )
    (net (code "29") (name "GPS_1PPS_DRV") (class "Default")
      (node (ref "R251") (pin "2") (pinfunction "2_2") (pintype "passive"))
      (node (ref "U201") (pin "37") (pinfunction "1PPS_37") (pintype "output"))
    )
    (net (code "30") (name "GPS_ANT") (class "Default")
      (node (ref "C291") (pin "1") (pinfunction "1_1") (pintype "passive"))
      (node (ref "L291") (pin "2") (pinfunction "2_2") (pintype "passive"))
      (node (ref "R291") (pin "1") (pinfunction "1_1") (pintype "passive"))
      (node (ref "X291") (pin "1") (pinfunction "1_1") (pintype "passive"))
    )
    (net (code "31") (name "GPS_PWR") (class "Default")
      (node (ref "L291") (pin "1") (pinfunction "1_1") (pintype "passive"))
      (node (ref "RPOLY291") (pin "1") (pinfunction "1_1") (pintype "passive"))
    )
    (net (code "32") (name "GPS_RF_IN") (class "Default")
      (node (ref "C292") (pin "1") (pinfunction "1_1") (pintype "passive"))
      (node (ref "R291") (pin "2") (pinfunction "2_2") (pintype "passive"))
      (node (ref "U201") (pin "35") (pinfunction "GPS_RF_IN_35") (pintype "input"))
    )
    (net (code "33") (name "GSM_ANT") (class "Default")
      (node (ref "C272") (pin "1") (pinfunction "1_1") (pintype "passive"))
      (node (ref "R271") (pin "2") (pinfunction "2_2") (pintype "passive"))
    )
    (net (code "34") (name "GSM_CTS") (class "Default")
      (node (ref "R223") (pin "2") (pinfunction "2_2") (pintype "passive"))
      (node (ref "U201") (pin "12") (pinfunction "CTS_12") (pintype "output"))
    )
    (net (code "35") (name "GSM_DCD") (class "Default")
      (node (ref "R222") (pin "2") (pinfunction "2_2") (pintype "passive"))
      (node (ref "U201") (pin "11") (pinfunction "DCD_11") (pintype "output"))
    )
    (net (code "36") (name "GSM_DTR") (class "Default")
      (node (ref "R171") (pin "2") (pinfunction "2_2") (pintype "passive"))
      (node (ref "U201") (pin "9") (pinfunction "DTR_9") (pintype "input"))
    )
    (net (code "37") (name "GSM_NETLIGHT") (class "Default")
      (node (ref "R231") (pin "2") (pinfunction "2_2") (pintype "passive"))
      (node (ref "U101") (pin "5") (pinfunction "PA7_5") (pintype "bidirectional"))
    )
    (net (code "38") (name "GSM_NETLIGHT_DRV") (class "Default")
      (node (ref "R231") (pin "1") (pinfunction "1_1") (pintype "passive"))
      (node (ref "U201") (pin "50") (pinfunction "NETLIGHT_50") (pintype "output"))
    )
    (net (code "39") (name "GSM_PCM_CLK") (class "Default")
      (node (ref "R141") (pin "2") (pinfunction "2_2") (pintype "passive"))
      (node (ref "U201") (pin "46") (pinfunction "PCM_CLK_46") (pintype "input"))
    )
    (net (code "40") (name "GSM_PCM_CLK_DRV") (class "Default")
      (node (ref "R141") (pin "1") (pinfunction "1_1") (pintype "passive"))
      (node (ref "U101") (pin "27") (pinfunction "PD1_27") (pintype "bidirectional"))
    )
    (net (code "41") (name "GSM_PCM_IN") (class "Default")
      (node (ref "R142") (pin "2") (pinfunction "2_2") (pintype "passive"))
      (node (ref "U201") (pin "47") (pinfunction "PCM_IN_47") (pintype "input"))
    )
    (net (code "42") (name "GSM_PCM_IN_DRV") (class "Default")
      (node (ref "R142") (pin "1") (pinfunction "1_1") (pintype "passive"))
      (node (ref "U101") (pin "29") (pinfunction "PD3_29") (pintype "bidirectional"))
    )
    (net (code "43") (name "GSM_PCM_OUT") (class "Default")
      (node (ref "R233") (pin "2") (pinfunction "2_2") (pintype "passive"))
      (node (ref "U101") (pin "28") (pinfunction "PD2_28") (pintype "bidirectional"))
    )
    (net (code "44") (name "GSM_PCM_OUT_DRV") (class "Default")
      (node (ref "R233") (pin "1") (pinfunction "1_1") (pintype "passive"))
      (node (ref "U201") (pin "48") (pinfunction "PCM_OUT_48") (pintype "output"))
    )
    (net (code "45") (name "GSM_PCM_SYNC") (class "Default")
      (node (ref "R234") (pin "2") (pinfunction "2_2") (pintype "passive"))
      (node (ref "U101") (pin "26") (pinfunction "PD0_26") (pintype "bidirectional"))
    )
    (net (code "46") (name "GSM_PCM_SYNC_DRV") (class "Default")
      (node (ref "R234") (pin "1") (pinfunction "1_1") (pintype "passive"))
      (node (ref "U201") (pin "45") (pinfunction "PCM_SYNC_45") (pintype "output"))
    )
    (net (code "47") (name "GSM_PWRKEY") (class "Default")
      (node (ref "R162") (pin "2") (pinfunction "2_2") (pintype "passive"))
      (node (ref "U201") (pin "8") (pinfunction "PWRKEY_8") (pintype "input"))
    )
    (net (code "48") (name "GSM_RESET") (class "Default")
      (node (ref "R163") (pin "2") (pinfunction "2_2") (pintype "passive"))
      (node (ref "U201") (pin "16") (pinfunction "RESET_16") (pintype "input"))
    )
    (net (code "49") (name "GSM_RF") (class "Default")
      (node (ref "C271") (pin "1") (pinfunction "1_1") (pintype "passive"))
      (node (ref "R271") (pin "1") (pinfunction "1_1") (pintype "passive"))
      (node (ref "U201") (pin "66") (pinfunction "GSM_RF_IN_66") (pintype "bidirectional"))
    )
    (net (code "50") (name "GSM_RF_SYNC") (class "Default")
      (node (ref "C141") (pin "1") (pinfunction "1_1") (pintype "passive"))
      (node (ref "R241") (pin "2") (pinfunction "2_2") (pintype "passive"))
      (node (ref "U101") (pin "4") (pinfunction "PA6_4") (pintype "bidirectional"))
    )
    (net (code "51") (name "GSM_RF_SYNC_DRV") (class "Default")
      (node (ref "R241") (pin "1") (pinfunction "1_1") (pintype "passive"))
      (node (ref "U201") (pin "63") (pinfunction "RF_SYNC_63") (pintype "output"))
    )
    (net (code "52") (name "GSM_RI") (class "Default")
      (node (ref "R221") (pin "2") (pinfunction "2_2") (pintype "passive"))
      (node (ref "U201") (pin "10") (pinfunction "RI_10") (pintype "output"))
    )
    (net (code "53") (name "GSM_RTS") (class "Default")
      (node (ref "R173") (pin "2") (pinfunction "2_2") (pintype "passive"))
      (node (ref "U201") (pin "13") (pinfunction "RTS_13") (pintype "input"))
    )
    (net (code "54") (name "GSM_RXD") (class "Default")
      (node (ref "R172") (pin "2") (pinfunction "2_2") (pintype "passive"))
      (node (ref "U201") (pin "15") (pinfunction "RXD_15") (pintype "input"))
    )
    (net (code "55") (name "GSM_STATUS") (class "Default")
      (node (ref "R232") (pin "2") (pinfunction "2_2") (pintype "passive"))
      (node (ref "U101") (pin "38") (pinfunction "PE2_38") (pintype "bidirectional"))
    )
    (net (code "56") (name "GSM_STATUS_DRV") (class "Default")
      (node (ref "R232") (pin "1") (pinfunction "1_1") (pintype "passive"))
      (node (ref "U201") (pin "49") (pinfunction "STATUS_49") (pintype "output"))
    )
    (net (code "57") (name "GSM_TXD") (class "Default")
      (node (ref "R224") (pin "2") (pinfunction "2_2") (pintype "passive"))
      (node (ref "U201") (pin "14") (pinfunction "TXD_14") (pintype "output"))
    )
    (net (code "58") (name "GSM_VDD_EXT") (class "Default")
      (node (ref "R161") (pin "2") (pinfunction "2_2") (pintype "passive"))
      (node (ref "U201") (pin "7") (pinfunction "VDD_EXT(2.8VOUT)_7") (pintype "output"))
    )
    (net (code "59") (name "I2C2_INT") (class "Default")
      (node (ref "R301") (pin "2") (pinfunction "2_2") (pintype "passive"))
      (node (ref "U101") (pin "6") (pinfunction "PB0_6") (pintype "bidirectional"))
    )
    (net (code "60") (name "IO_ADC4") (class "Default")
      (node (ref "U101") (pin "2") (pinfunction "PA4_2") (pintype "bidirectional"))
      (node (ref "X181") (pin "3") (pinfunction "3_3") (pintype "passive"))
    )
    (net (code "61") (name "IO_ADC5") (class "Default")
      (node (ref "U101") (pin "3") (pinfunction "PA5_3") (pintype "bidirectional"))
      (node (ref "X181") (pin "5") (pinfunction "5_5") (pintype "passive"))
    )
    (net (code "62") (name "IO_DAC0") (class "Default")
      (node (ref "U101") (pin "8") (pinfunction "PB2_8") (pintype "bidirectional"))
      (node (ref "X181") (pin "4") (pinfunction "4_4") (pintype "passive"))
    )
    (net (code "63") (name "IO_DAC1") (class "Default")
      (node (ref "U101") (pin "9") (pinfunction "PB3_9") (pintype "bidirectional"))
      (node (ref "X181") (pin "6") (pinfunction "6_6") (pintype "passive"))
    )
    (net (code "64") (name "IO_OC1A") (class "Default")
      (node (ref "U101") (pin "30") (pinfunction "PD4_30") (pintype "bidirectional"))
      (node (ref "X181") (pin "2") (pinfunction "2_2") (pintype "passive"))
    )
    (net (code "65") (name "MPU_INT") (class "Default")
      (node (ref "R301") (pin "1") (pinfunction "1_1") (pintype "passive"))
      (node (ref "U301") (pin "12") (pinfunction "INT_12") (pintype "output"))
    )
    (net (code "66") (name "Net-(C611-Pad1)") (class "Default")
      (node (ref "C611") (pin "1") (pinfunction "1_1") (pintype "passive"))
      (node (ref "U601") (pin "1") (pinfunction "VDD_ANA_1") (pintype "passive"))
    )
    (net (code "67") (name "Net-(C612-Pad1)") (class "Default")
      (node (ref "C612") (pin "1") (pinfunction "1_1") (pintype "passive"))
      (node (ref "U601") (pin "5") (pinfunction "VDD_ANA_5") (pintype "passive"))
    )
    (net (code "68") (name "Net-(C701-Pad1)") (class "Default")
      (node (ref "C701") (pin "1") (pinfunction "1_1") (pintype "passive"))
      (node (ref "R701") (pin "1") (pinfunction "1_1") (pintype "passive"))
      (node (ref "X701") (pin "JSHIELD") (pinfunction "SHIELD_JSHIELD") (pintype "passive"))
      (node (ref "X701") (pin "JSHIELD@2") (pinfunction "SHIELD_JSHIELD@2") (pintype "passive"))
      (node (ref "X701") (pin "JSHIELD@3") (pinfunction "SHIELD_JSHIELD@3") (pintype "passive"))
      (node (ref "X701") (pin "JSHIELD@4") (pinfunction "SHIELD_JSHIELD@4") (pintype "passive"))
      (node (ref "X701") (pin "JSHIELD@5") (pinfunction "SHIELD_JSHIELD@5") (pintype "passive"))
      (node (ref "X701") (pin "JSHIELD@6") (pinfunction "SHIELD_JSHIELD@6") (pintype "passive"))
    )
    (net (code "69") (name "Net-(Q651-2)") (class "Default")
      (node (ref "Q651") (pin "3") (pinfunction "2_3") (pintype "passive"))
      (node (ref "U601") (pin "19") (pinfunction "CLK16N_19") (pintype "passive"))
    )
    (net (code "70") (name "Net-(RPOLY901-Pad1)") (class "Default")
      (node (ref "RPOLY901") (pin "1") (pinfunction "1_1") (pintype "passive"))
      (node (ref "X901") (pin "1") (pinfunction "1_1") (pintype "passive"))
    )
    (net (code "71") (name "Net-(U101A-TOSC1)") (class "Default")
      (node (ref "Q101") (pin "2") (pinfunction "2_2") (pintype "passive"))
      (node (ref "U101") (pin "43") (pinfunction "TOSC1_43") (pintype "passive"))
    )
    (net (code "72") (name "Net-(U101A-TOSC2)") (class "Default")
      (node (ref "Q101") (pin "1") (pinfunction "1_1") (pintype "passive"))
      (node (ref "U101") (pin "42") (pinfunction "TOSC2_42") (pintype "passive"))
    )
    (net (code "73") (name "Net-(U301-REGOUT)") (class "Default")
      (node (ref "C302") (pin "1") (pinfunction "1_1") (pintype "passive"))
      (node (ref "U301") (pin "10") (pinfunction "REGOUT_10") (pintype "passive"))
    )
    (net (code "74") (name "Net-(U601-CLK16P)") (class "Default")
      (node (ref "Q651") (pin "1") (pinfunction "1_1") (pintype "passive"))
      (node (ref "U601") (pin "20") (pinfunction "CLK16P_20") (pintype "passive"))
    )
    (net (code "75") (name "Net-(U1021--IN)") (class "Default")
      (node (ref "R1021") (pin "1") (pinfunction "1_1") (pintype "passive"))
      (node (ref "U1021") (pin "4") (pinfunction "-IN_4") (pintype "input"))
    )
    (net (code "76") (name "Net-(U1111-VIN)") (class "Default")
      (node (ref "C1111") (pin "1") (pinfunction "1_1") (pintype "passive"))
      (node (ref "C1121") (pin "1") (pinfunction "1_1") (pintype "passive"))
      (node (ref "D1121") (pin "C") (pinfunction "C_C") (pintype "passive"))
      (node (ref "D1122") (pin "C") (pinfunction "C_C") (pintype "passive"))
      (node (ref "R1113") (pin "1") (pinfunction "1_1") (pintype "passive"))
      (node (ref "U1111") (pin "5") (pinfunction "VIN_5") (pintype "power_in"))
      (node (ref "U1121") (pin "3") (pinfunction "EN_3") (pintype "input"))
      (node (ref "U1121") (pin "4") (pinfunction "VIN_4") (pintype "power_in"))
    )
    (net (code "77") (name "Net-(X701-J_D+)") (class "Default")
      (node (ref "R723") (pin "1") (pinfunction "1_1") (pintype "passive"))
      (node (ref "R724") (pin "1") (pinfunction "1_1") (pintype "passive"))
      (node (ref "X701") (pin "D+") (pinfunction "J_D+_D+") (pintype "bidirectional"))
    )
    (net (code "78") (name "Net-(X701-J_D-)") (class "Default")
      (node (ref "R721") (pin "1") (pinfunction "1_1") (pintype "passive"))
      (node (ref "R722") (pin "1") (pinfunction "1_1") (pintype "passive"))
      (node (ref "X701") (pin "D-") (pinfunction "J_D-_D-") (pintype "bidirectional"))
    )
    (net (code "79") (name "Net-(X701-J_ID)") (class "Default")
      (node (ref "R725") (pin "1") (pinfunction "1_1") (pintype "passive"))
      (node (ref "X701") (pin "ID") (pinfunction "J_ID_ID") (pintype "bidirectional"))
    )
    (net (code "80") (name "Net-(X701-J_VUSB)") (class "Default")
      (node (ref "RPOLY711") (pin "1") (pinfunction "1_1") (pintype "passive"))
      (node (ref "X701") (pin "VBUS") (pinfunction "J_VUSB_VBUS") (pintype "power_in"))
    )
    (net (code "81") (name "PDI_CLK") (class "Default")
      (node (ref "R112") (pin "1") (pinfunction "1_1") (pintype "passive"))
      (node (ref "R132") (pin "1") (pinfunction "1_1") (pintype "passive"))
      (node (ref "X111") (pin "6") (pinfunction "6_6") (pintype "passive"))
      (node (ref "X131") (pin "5") (pinfunction "5_5") (pintype "passive"))
    )
    (net (code "82") (name "PDI_CLK_CPU") (class "Default")
      (node (ref "R132") (pin "2") (pinfunction "2_2") (pintype "passive"))
      (node (ref "U101") (pin "57") (pinfunction "~{RESET}/PDI_CLK_57") (pintype "input"))
    )
    (net (code "83") (name "PDI_DATA") (class "Default")
      (node (ref "R131") (pin "1") (pinfunction "1_1") (pintype "passive"))
      (node (ref "X131") (pin "1") (pinfunction "1_1") (pintype "passive"))
    )
    (net (code "84") (name "PDI_DATA_CPU") (class "Default")
      (node (ref "R131") (pin "2") (pinfunction "2_2") (pintype "passive"))
      (node (ref "U101") (pin "56") (pinfunction "PDI_DATA_56") (pintype "input"))
    )
    (net (code "85") (name "POWERED_GSM") (class "Default")
      (node (ref "R161") (pin "1") (pinfunction "1_1") (pintype "passive"))
      (node (ref "U101") (pin "39") (pinfunction "PE3_39") (pintype "bidirectional"))
    )
    (net (code "86") (name "PWRKEY_GSM") (class "Default")
      (node (ref "R162") (pin "1") (pinfunction "1_1") (pintype "passive"))
      (node (ref "U101") (pin "40") (pinfunction "PE4_40") (pintype "bidirectional"))
    )
    (net (code "87") (name "RESET_GSM") (class "Default")
      (node (ref "R163") (pin "1") (pinfunction "1_1") (pintype "passive"))
      (node (ref "U101") (pin "41") (pinfunction "PE5_41") (pintype "bidirectional"))
    )
    (net (code "88") (name "RI1") (class "Default")
      (node (ref "R221") (pin "1") (pinfunction "1_1") (pintype "passive"))
      (node (ref "U101") (pin "50") (pinfunction "PF4_50") (pintype "bidirectional"))
    )
    (net (code "89") (name "RTS1") (class "Default")
      (node (ref "R223") (pin "1") (pinfunction "1_1") (pintype "passive"))
      (node (ref "U101") (pin "54") (pinfunction "PF6_54") (pintype "bidirectional"))
    )
    (net (code "90") (name "RXD1") (class "Default")
      (node (ref "R224") (pin "1") (pinfunction "1_1") (pintype "passive"))
      (node (ref "U101") (pin "48") (pinfunction "PF2_48") (pintype "bidirectional"))
    )
    (net (code "91") (name "SCL1") (class "Default")
      (node (ref "R212") (pin "2") (pinfunction "2_2") (pintype "passive"))
      (node (ref "R401") (pin "1") (pinfunction "1_1") (pintype "passive"))
      (node (ref "U101") (pin "37") (pinfunction "PE1_37") (pintype "bidirectional"))
      (node (ref "U201") (pin "39") (pinfunction "SCL_39") (pintype "bidirectional"))
      (node (ref "U301") (pin "23") (pinfunction "SCL/SCLK_23") (pintype "input"))
      (node (ref "U401") (pin "8") (pinfunction "SCL_SCLK_8") (pintype "input"))
      (node (ref "U501") (pin "4") (pinfunction "SCL_4") (pintype "input"))
    )
    (net (code "92") (name "SCL2") (class "Default")
      (node (ref "U101") (pin "17") (pinfunction "PC1_17") (pintype "bidirectional"))
      (node (ref "X121") (pin "2") (pinfunction "2_2") (pintype "passive"))
    )
    (net (code "93") (name "SDA1") (class "Default")
      (node (ref "R211") (pin "2") (pinfunction "2_2") (pintype "passive"))
      (node (ref "R402") (pin "1") (pinfunction "1_1") (pintype "passive"))
      (node (ref "U101") (pin "36") (pinfunction "PE0_36") (pintype "bidirectional"))
      (node (ref "U201") (pin "38") (pinfunction "SDA_38") (pintype "bidirectional"))
      (node (ref "U301") (pin "24") (pinfunction "SDA/SDI_24") (pintype "bidirectional"))
      (node (ref "U401") (pin "7") (pinfunction "SDI_SDA_7") (pintype "bidirectional"))
      (node (ref "U501") (pin "1") (pinfunction "SDA_1") (pintype "bidirectional"))
    )
    (net (code "94") (name "SDA2") (class "Default")
      (node (ref "U101") (pin "16") (pinfunction "PC0_16") (pintype "bidirectional"))
      (node (ref "X121") (pin "4") (pinfunction "4_4") (pintype "passive"))
    )
    (net (code "95") (name "SIM_CLK") (class "Default")
      (node (ref "U201") (pin "31") (pinfunction "SIM_CLK_31") (pintype "output"))
      (node (ref "X801") (pin "S3") (pinfunction "S3_S3") (pintype "input"))
    )
    (net (code "96") (name "SIM_IO") (class "Default")
      (node (ref "U201") (pin "30") (pinfunction "SIM_DATA_30") (pintype "bidirectional"))
      (node (ref "X801") (pin "S7") (pinfunction "S7_S7") (pintype "bidirectional"))
    )
    (net (code "97") (name "SIM_RST") (class "Default")
      (node (ref "U201") (pin "32") (pinfunction "SIM_RST_32") (pintype "output"))
      (node (ref "X801") (pin "S2") (pinfunction "S2_S2") (pintype "bidirectional"))
    )
    (net (code "98") (name "SIM_VBUS") (class "Default")
      (node (ref "JP201") (pin "2") (pinfunction "2_2") (pintype "passive"))
      (node (ref "U201") (pin "25") (pinfunction "VBUS_25") (pintype "power_in"))
    )
    (net (code "99") (name "SIM_VCC") (class "Default")
      (node (ref "U201") (pin "29") (pinfunction "SIM_VDD_29") (pintype "power_in"))
      (node (ref "X801") (pin "S1") (pinfunction "S1_S1") (pintype "power_in"))
    )
    (net (code "100") (name "SIM_VPP") (class "Default")
      (node (ref "U201") (pin "33") (pinfunction "SIM_PRE_33") (pintype "input"))
      (node (ref "X801") (pin "S6") (pinfunction "S6_S6") (pintype "power_in"))
    )
    (net (code "101") (name "SW") (class "Default")
      (node (ref "D1111") (pin "C") (pinfunction "C_C") (pintype "passive"))
      (node (ref "L1111") (pin "2") (pinfunction "2_2") (pintype "passive"))
      (node (ref "U1111") (pin "1") (pinfunction "SW_1") (pintype "output"))
    )
    (net (code "102") (name "T4") (class "Default")
      (node (ref "X801") (pin "T4") (pinfunction "T4_T4") (pintype "power_in"))
    )
    (net (code "103") (name "TCK") (class "Default")
      (node (ref "U101") (pin "12") (pinfunction "PB6_12") (pintype "bidirectional"))
      (node (ref "X111") (pin "1") (pinfunction "1_1") (pintype "passive"))
    )
    (net (code "104") (name "TCXO_20MHZ") (class "Default")
      (node (ref "R1013") (pin "2") (pinfunction "2_2") (pintype "passive"))
      (node (ref "U101") (pin "59") (pinfunction "PR1_59") (pintype "bidirectional"))
    )
    (net (code "105") (name "TDI") (class "Default")
      (node (ref "U101") (pin "11") (pinfunction "PB5_11") (pintype "bidirectional"))
      (node (ref "X111") (pin "9") (pinfunction "9_9") (pintype "passive"))
    )
    (net (code "106") (name "TDO") (class "Default")
      (node (ref "U101") (pin "13") (pinfunction "PB7_13") (pintype "bidirectional"))
      (node (ref "X111") (pin "3") (pinfunction "3_3") (pintype "passive"))
    )
    (net (code "107") (name "TMS") (class "Default")
      (node (ref "U101") (pin "10") (pinfunction "PB4_10") (pintype "bidirectional"))
      (node (ref "X111") (pin "5") (pinfunction "5_5") (pintype "passive"))
    )
    (net (code "108") (name "TRSH") (class "Default")
      (node (ref "C1011") (pin "1") (pinfunction "1_1") (pintype "passive"))
      (node (ref "R1011") (pin "2") (pinfunction "2_2") (pintype "passive"))
      (node (ref "R1012") (pin "1") (pinfunction "1_1") (pintype "passive"))
      (node (ref "U1011") (pin "4") (pinfunction "-IN_4") (pintype "input"))
    )
    (net (code "109") (name "TXD1") (class "Default")
      (node (ref "R172") (pin "1") (pinfunction "1_1") (pintype "passive"))
      (node (ref "U101") (pin "49") (pinfunction "PF3_49") (pintype "bidirectional"))
    )
    (net (code "110") (name "USB_D_N") (class "Default")
      (node (ref "D722") (pin "C") (pinfunction "C_C") (pintype "passive"))
      (node (ref "R722") (pin "2") (pinfunction "2_2") (pintype "passive"))
      (node (ref "U101") (pin "32") (pinfunction "PD6_32") (pintype "bidirectional"))
    )
    (net (code "111") (name "USB_D_P") (class "Default")
      (node (ref "D721") (pin "C") (pinfunction "C_C") (pintype "passive"))
      (node (ref "R723") (pin "2") (pinfunction "2_2") (pintype "passive"))
      (node (ref "U101") (pin "33") (pinfunction "PD7_33") (pintype "bidirectional"))
    )
    (net (code "112") (name "USB_ID") (class "Default")
      (node (ref "R725") (pin "2") (pinfunction "2_2") (pintype "passive"))
      (node (ref "U101") (pin "7") (pinfunction "PB1_7") (pintype "bidirectional"))
    )
    (net (code "113") (name "USB_RESET") (class "Default")
      (node (ref "R151") (pin "2") (pinfunction "2_2") (pintype "passive"))
      (node (ref "R721") (pin "2") (pinfunction "2_2") (pintype "passive"))
    )
    (net (code "114") (name "USB_RESET_DRV") (class "Default")
      (node (ref "R151") (pin "1") (pinfunction "1_1") (pintype "passive"))
      (node (ref "U101") (pin "31") (pinfunction "PD5_31") (pintype "bidirectional"))
    )
    (net (code "115") (name "VBAT") (class "Default")
      (node (ref "C201") (pin "1") (pinfunction "1_1") (pintype "passive"))
      (node (ref "C901") (pin "1") (pinfunction "1_1") (pintype "passive"))
      (node (ref "D1122") (pin "A") (pinfunction "A_A") (pintype "passive"))
      (node (ref "D201") (pin "C") (pinfunction "C_C") (pintype "passive"))
      (node (ref "R1132") (pin "1") (pinfunction "1_1") (pintype "passive"))
      (node (ref "RPOLY901") (pin "2") (pinfunction "2_2") (pintype "passive"))
      (node (ref "U201") (pin "4") (pinfunction "VBAT_4") (pintype "power_in"))
      (node (ref "U201") (pin "5") (pinfunction "VBAT_5") (pintype "power_in"))
      (node (ref "U201") (pin "6") (pinfunction "VBAT_6") (pintype "power_in"))
    )
    (net (code "116") (name "VREF") (class "Default")
      (node (ref "R111") (pin "1") (pinfunction "1_1") (pintype "passive"))
      (node (ref "X111") (pin "4") (pinfunction "4_4") (pintype "passive"))
    )
    (net (code "117") (name "XO_AMP") (class "Default")
      (node (ref "R1013") (pin "1") (pinfunction "1_1") (pintype "passive"))
      (node (ref "U1011") (pin "1") (pinfunction "OUT_1") (pintype "output"))
    )
    (net (code "118") (name "XO_DRV") (class "Default")
      (node (ref "U1001") (pin "3") (pinfunction "OUT_3") (pintype "output"))
      (node (ref "U1011") (pin "3") (pinfunction "+IN_3") (pintype "input"))
    )
    (net (code "119") (name "XO_LP") (class "Default")
      (node (ref "C1001") (pin "1") (pinfunction "1_1") (pintype "passive"))
      (node (ref "R1001") (pin "2") (pinfunction "2_2") (pintype "passive"))
      (node (ref "R1002") (pin "1") (pinfunction "1_1") (pintype "passive"))
      (node (ref "U1021") (pin "3") (pinfunction "+IN_3") (pintype "input"))
    )
    (net (code "120") (name "XO_VC") (class "Default")
      (node (ref "R1002") (pin "2") (pinfunction "2_2") (pintype "passive"))
      (node (ref "U1001") (pin "1") (pinfunction "VC_1") (pintype "input"))
    )
    (net (code "121") (name "XO_VC_PWM") (class "Default")
      (node (ref "R1001") (pin "1") (pinfunction "1_1") (pintype "passive"))
      (node (ref "U101") (pin "18") (pinfunction "PC2_18") (pintype "bidirectional"))
    )
    (net (code "122") (name "unconnected-(U201-ADC1-Pad23)") (class "Default")
      (node (ref "U201") (pin "23") (pinfunction "ADC1_23") (pintype "input"))
    )
    (net (code "123") (name "unconnected-(U201-ADC2-Pad24)") (class "Default")
      (node (ref "U201") (pin "24") (pinfunction "ADC2_24") (pintype "input"))
    )
    (net (code "124") (name "unconnected-(U201-COL0-Pad62)") (class "Default")
      (node (ref "U201") (pin "62") (pinfunction "COL0_62") (pintype "input"))
    )
    (net (code "125") (name "unconnected-(U201-COL1-Pad61)") (class "Default")
      (node (ref "U201") (pin "61") (pinfunction "COL1_61") (pintype "input"))
    )
    (net (code "126") (name "unconnected-(U201-COL2-Pad60)") (class "Default")
      (node (ref "U201") (pin "60") (pinfunction "COL2_60") (pintype "input"))
    )
    (net (code "127") (name "unconnected-(U201-COL3-Pad59)") (class "Default")
      (node (ref "U201") (pin "59") (pinfunction "COL3_59") (pintype "input"))
    )
    (net (code "128") (name "unconnected-(U201-GPIO5-Pad43)") (class "Default")
      (node (ref "U201") (pin "43") (pinfunction "GPIO5_43") (pintype "bidirectional"))
    )
    (net (code "129") (name "unconnected-(U201-GPIO6-Pad44)") (class "Default")
      (node (ref "U201") (pin "44") (pinfunction "GPIO6_44") (pintype "bidirectional"))
    )
    (net (code "130") (name "unconnected-(U201-MIC1N-Pad20)") (class "Default")
      (node (ref "U201") (pin "20") (pinfunction "MIC1N_20") (pintype "input"))
    )
    (net (code "131") (name "unconnected-(U201-MIC1P-Pad19)") (class "Default")
      (node (ref "U201") (pin "19") (pinfunction "MIC1P_19") (pintype "input"))
    )
    (net (code "132") (name "unconnected-(U201-PWM1-Pad42)") (class "Default")
      (node (ref "U201") (pin "42") (pinfunction "PWM1_42") (pintype "output"))
    )
    (net (code "133") (name "unconnected-(U201-PWM2-Pad41)") (class "Default")
      (node (ref "U201") (pin "41") (pinfunction "PWM2_41") (pintype "output"))
    )
    (net (code "134") (name "unconnected-(U201-ROW0-Pad58)") (class "Default")
      (node (ref "U201") (pin "58") (pinfunction "ROW0_58") (pintype "output"))
    )
    (net (code "135") (name "unconnected-(U201-ROW1-Pad57)") (class "Default")
      (node (ref "U201") (pin "57") (pinfunction "ROW1_57") (pintype "output"))
    )
    (net (code "136") (name "unconnected-(U201-ROW2-Pad56)") (class "Default")
      (node (ref "U201") (pin "56") (pinfunction "ROW2_56") (pintype "output"))
    )
    (net (code "137") (name "unconnected-(U201-ROW3-Pad55)") (class "Default")
      (node (ref "U201") (pin "55") (pinfunction "ROW3_55") (pintype "output"))
    )
    (net (code "138") (name "unconnected-(U201-SPK1N-Pad22)") (class "Default")
      (node (ref "U201") (pin "22") (pinfunction "SPK1N_22") (pintype "output"))
    )
    (net (code "139") (name "unconnected-(U201-SPK1P-Pad21)") (class "Default")
      (node (ref "U201") (pin "21") (pinfunction "SPK1P_21") (pintype "output"))
    )
    (net (code "140") (name "unconnected-(U201-USB_DM-Pad27)") (class "Default")
      (node (ref "U201") (pin "27") (pinfunction "USB_DM_27") (pintype "bidirectional"))
    )
    (net (code "141") (name "unconnected-(U201-USB_DP-Pad26)") (class "Default")
      (node (ref "U201") (pin "26") (pinfunction "USB_DP_26") (pintype "bidirectional"))
    )
    (net (code "142") (name "unconnected-(U301-AUX_CL-Pad7)") (class "Default")
      (node (ref "U301") (pin "7") (pinfunction "AUX_CL_7") (pintype "output"))
    )
    (net (code "143") (name "unconnected-(U301-AUX_DA-Pad21)") (class "Default")
      (node (ref "U301") (pin "21") (pinfunction "AUX_DA_21") (pintype "bidirectional"))
    )
    (net (code "144") (name "unconnected-(U401-NC-Pad5)") (class "Default")
      (node (ref "U401") (pin "5") (pinfunction "NC_5") (pintype "no_connect"))
    )
    (net (code "145") (name "unconnected-(U401-SDO-Pad6)") (class "Default")
      (node (ref "U401") (pin "6") (pinfunction "SDO_6") (pintype "output"))
    )
    (net (code "146") (name "unconnected-(U501-ALERT-Pad3)") (class "Default")
      (node (ref "U501") (pin "3") (pinfunction "ALERT_3") (pintype "output"))
    )
    (net (code "147") (name "unconnected-(U601-FILT-Pad6)") (class "Default")
      (node (ref "U601") (pin "6") (pinfunction "FILT_6") (pintype "passive"))
    )
    (net (code "148") (name "unconnected-(U601-SYSCLK-Pad9)") (class "Default")
      (node (ref "U601") (pin "9") (pinfunction "SYSCLK_9") (pintype "bidirectional"))
    )
    (net (code "149") (name "unconnected-(U601-TCXO_EN-Pad15)") (class "Default")
      (node (ref "U601") (pin "15") (pinfunction "TCXO_EN_15") (pintype "bidirectional"))
    )
    (net (code "150") (name "unconnected-(U1121-REF-Pad1)") (class "Default")
      (node (ref "U1121") (pin "1") (pinfunction "REF_1") (pintype "no_connect"))
    )
    (net (code "151") (name "unconnected-(X111-Pad8)") (class "Default")
      (node (ref "X111") (pin "8") (pinfunction "8_8") (pintype "passive"))
    )
    (net (code "152") (name "unconnected-(X131-Pad3)") (class "Default")
      (node (ref "X131") (pin "3") (pinfunction "3_3") (pintype "passive"))
    )
    (net (code "153") (name "unconnected-(X131-Pad4)") (class "Default")
      (node (ref "X131") (pin "4") (pinfunction "4_4") (pintype "passive"))
    )
    (net (code "154") (name "unconnected-(X801-PadS4)") (class "Default")
      (node (ref "X801") (pin "S4") (pinfunction "S4_S4") (pintype "passive"))
    )
    (net (code "155") (name "unconnected-(X801-PadS8)") (class "Default")
      (node (ref "X801") (pin "S8") (pinfunction "S8_S8") (pintype "passive"))
    )
    (net (code "156") (name "unconnected-(X801-PadSW)") (class "Default")
      (node (ref "X801") (pin "SW") (pinfunction "SW_SW") (pintype "passive"))
    )
    (net (code "157") (name "unconnected-(X801-PadT1)") (class "Default")
      (node (ref "X801") (pin "T1") (pinfunction "T1_T1") (pintype "bidirectional"))
    )
    (net (code "158") (name "unconnected-(X801-PadT2)") (class "Default")
      (node (ref "X801") (pin "T2") (pinfunction "T2_T2") (pintype "bidirectional"))
    )
    (net (code "159") (name "unconnected-(X801-PadT3)") (class "Default")
      (node (ref "X801") (pin "T3") (pinfunction "T3_T3") (pintype "bidirectional"))
    )
    (net (code "160") (name "unconnected-(X801-PadT5)") (class "Default")
      (node (ref "X801") (pin "T5") (pinfunction "T5_T5") (pintype "input"))
    )
    (net (code "161") (name "unconnected-(X801-PadT7)") (class "Default")
      (node (ref "X801") (pin "T7") (pinfunction "T7_T7") (pintype "bidirectional"))
    )
    (net (code "162") (name "unconnected-(X801-PadT8)") (class "Default")
      (node (ref "X801") (pin "T8") (pinfunction "T8_T8") (pintype "bidirectional"))
    )
    (net (code "163") (name "unconnected-(X901-Pad2)") (class "Default")
      (node (ref "X901") (pin "2") (pinfunction "2_2") (pintype "passive"))
    )
  )
)
